# 010.net
KiCad netlist of a schematic drawn in EAGLE
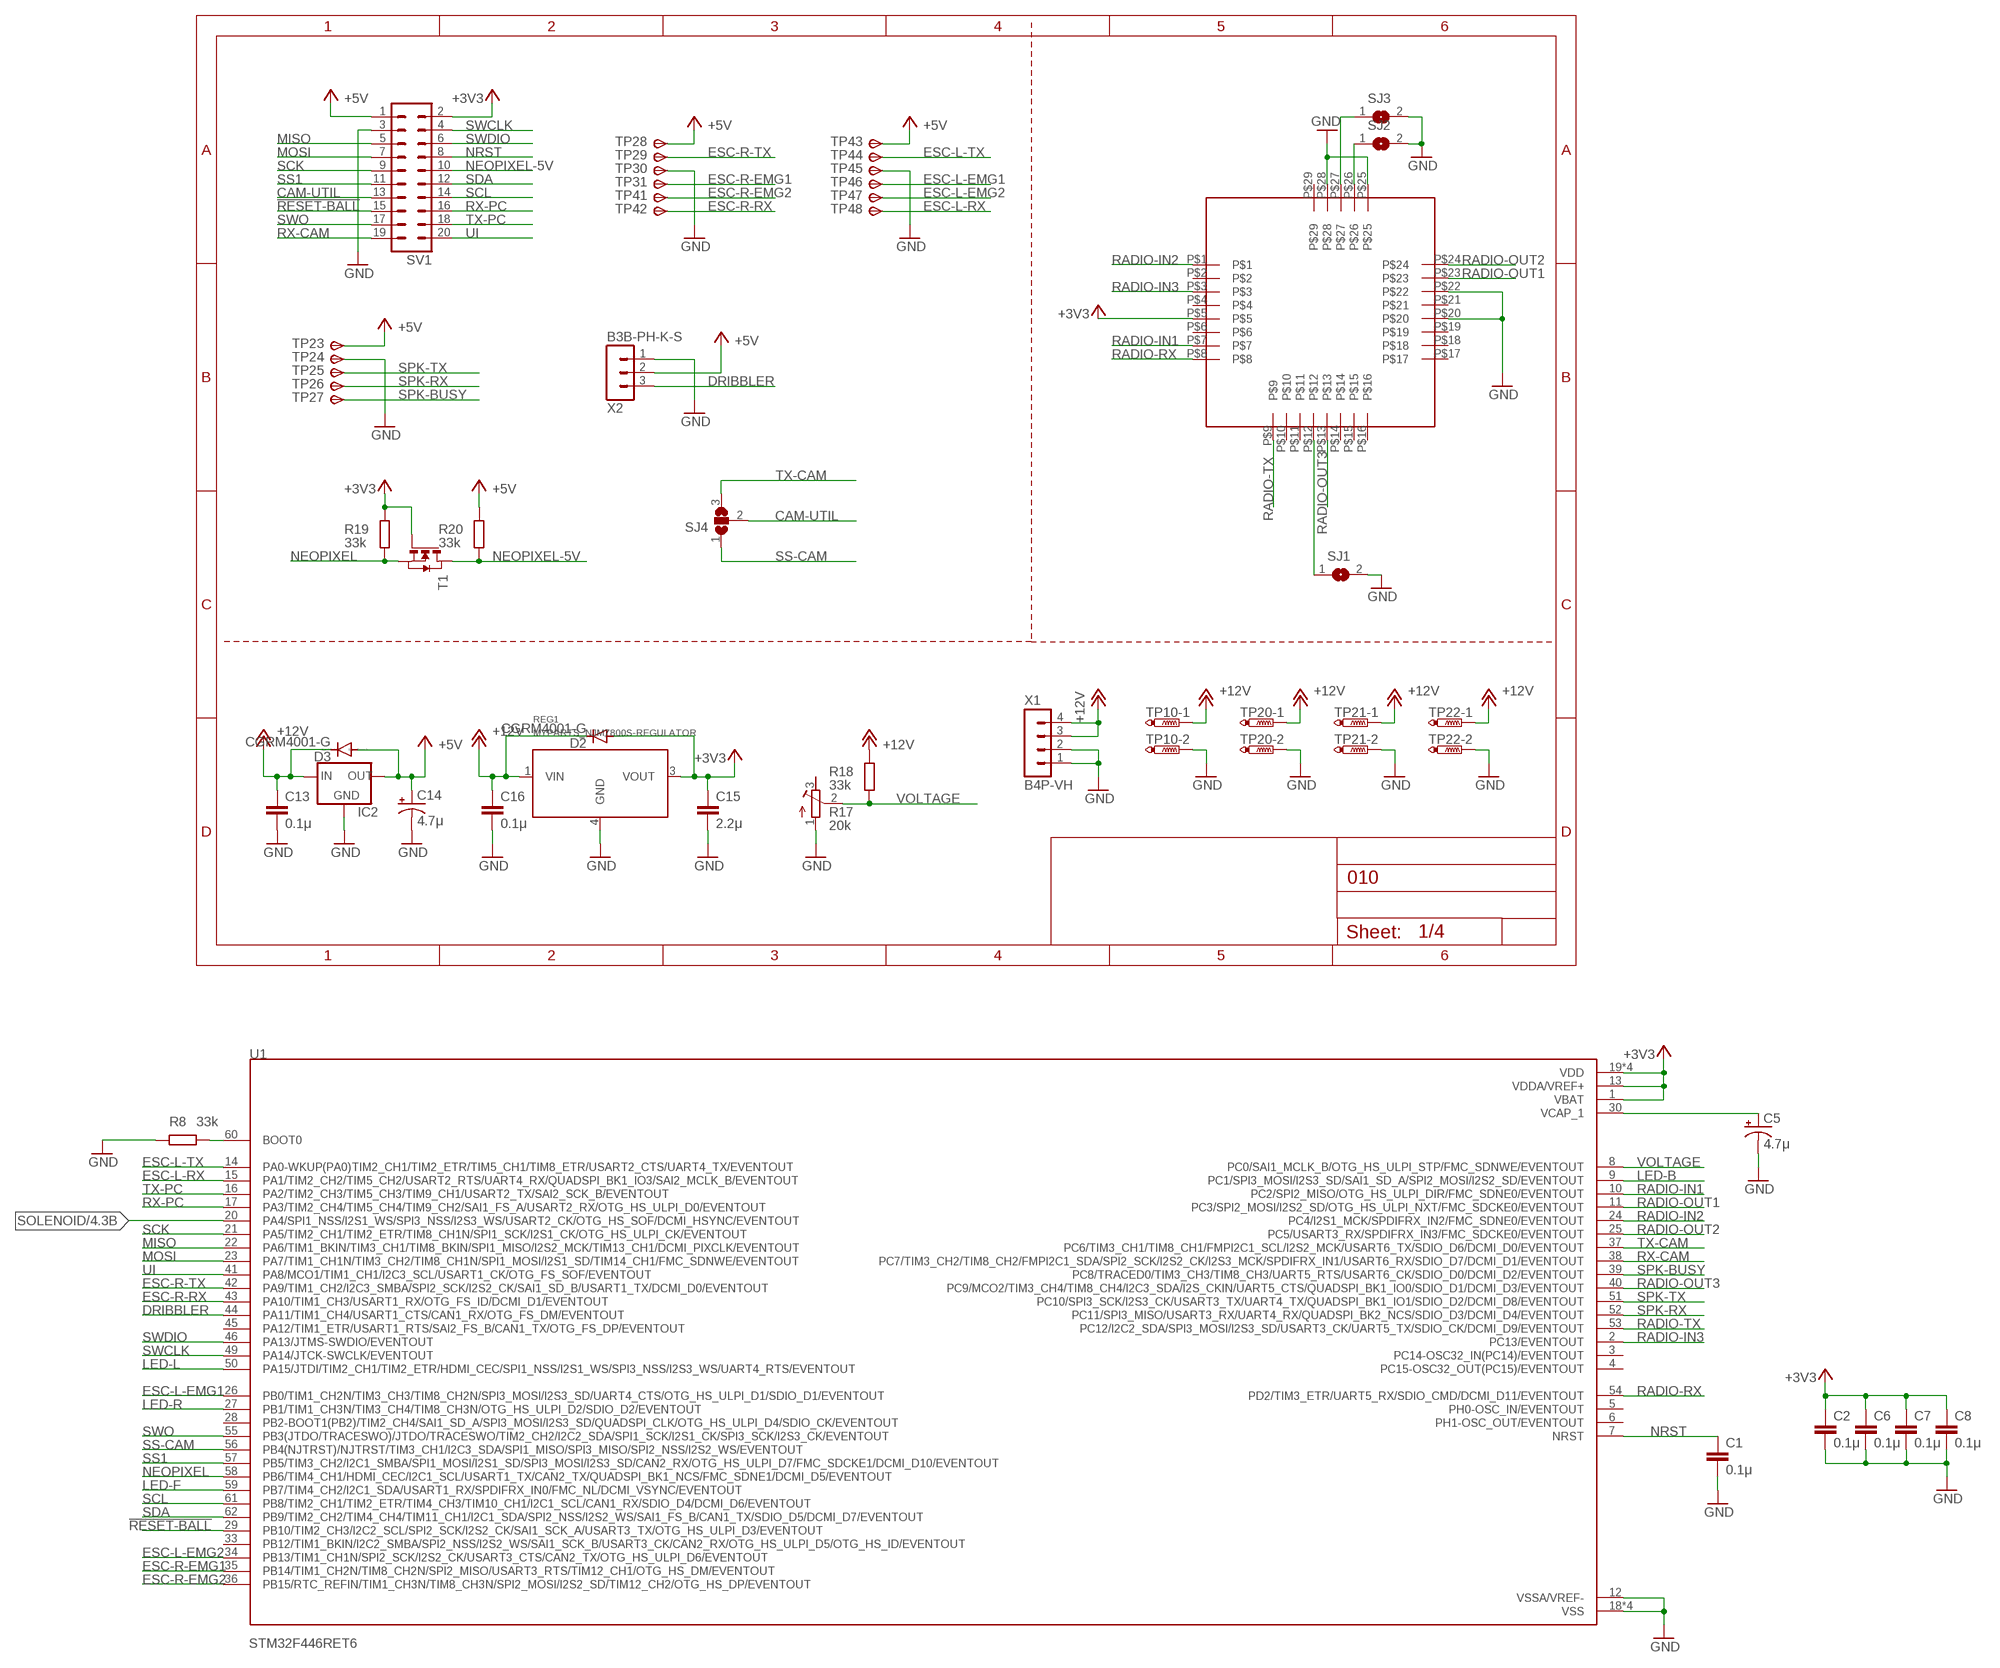
[diagram p0: schematic, sheet 1]
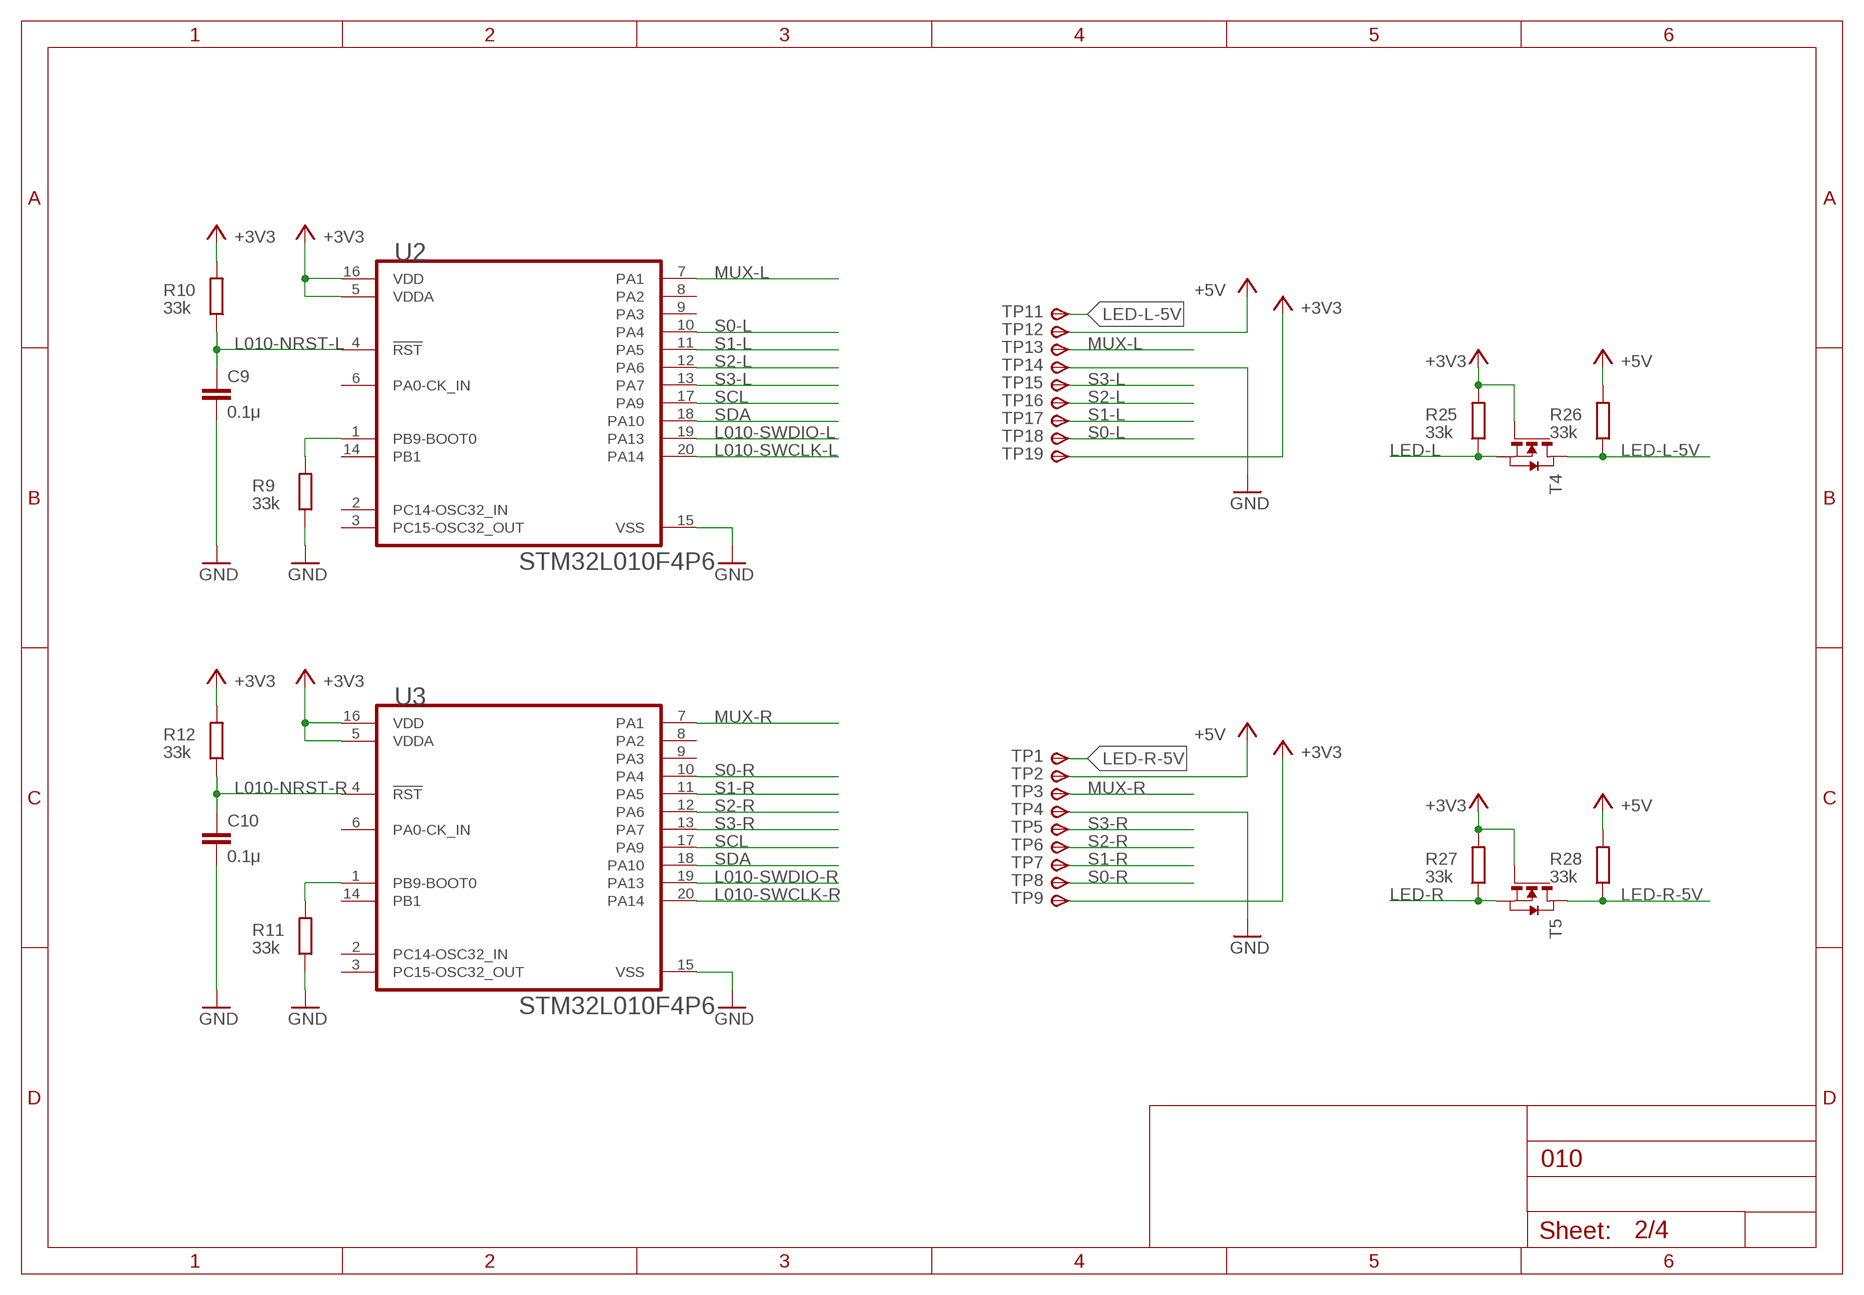
[diagram p1: schematic, sheet 2]
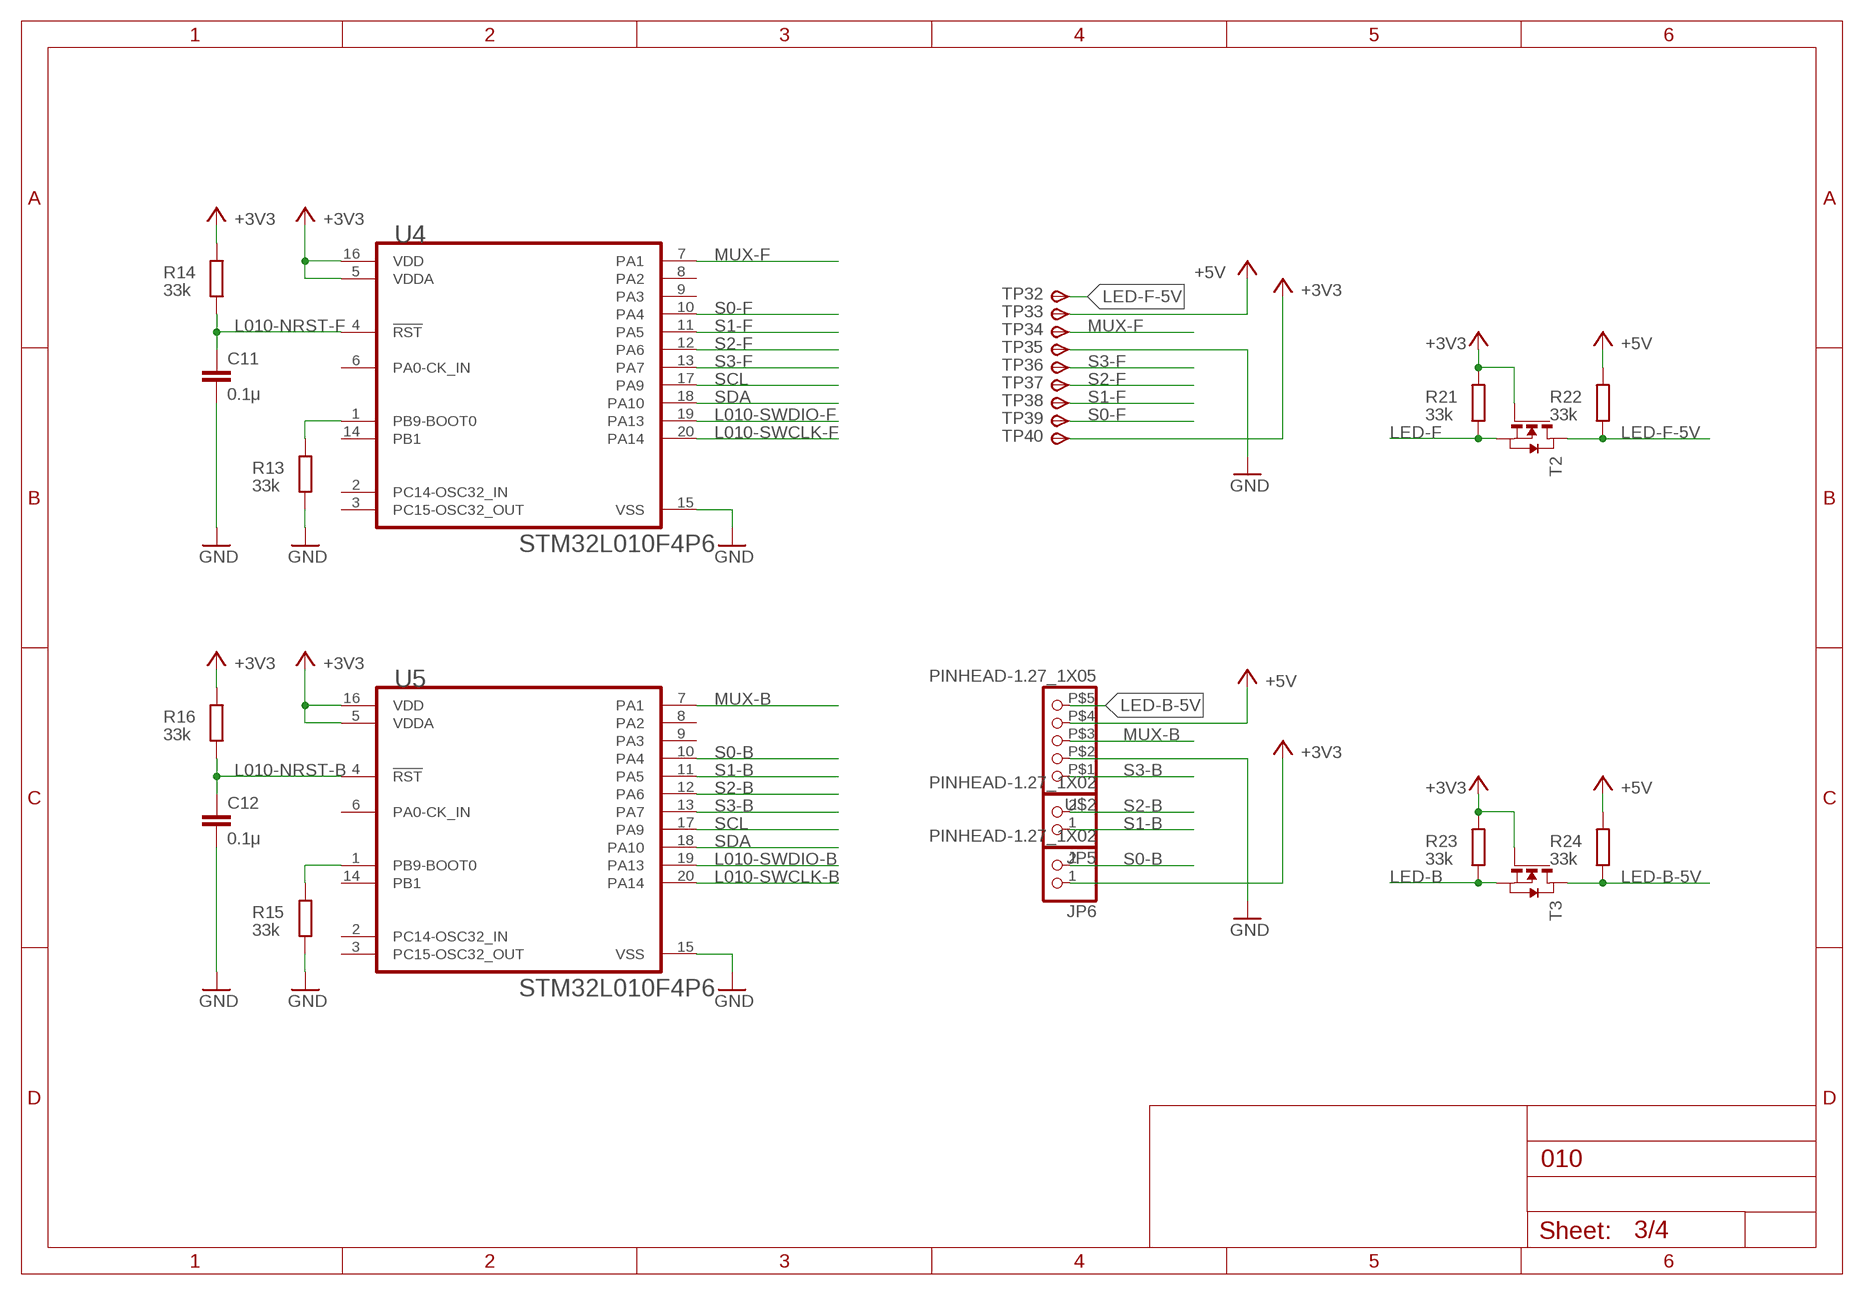
[diagram p2: schematic, sheet 3]
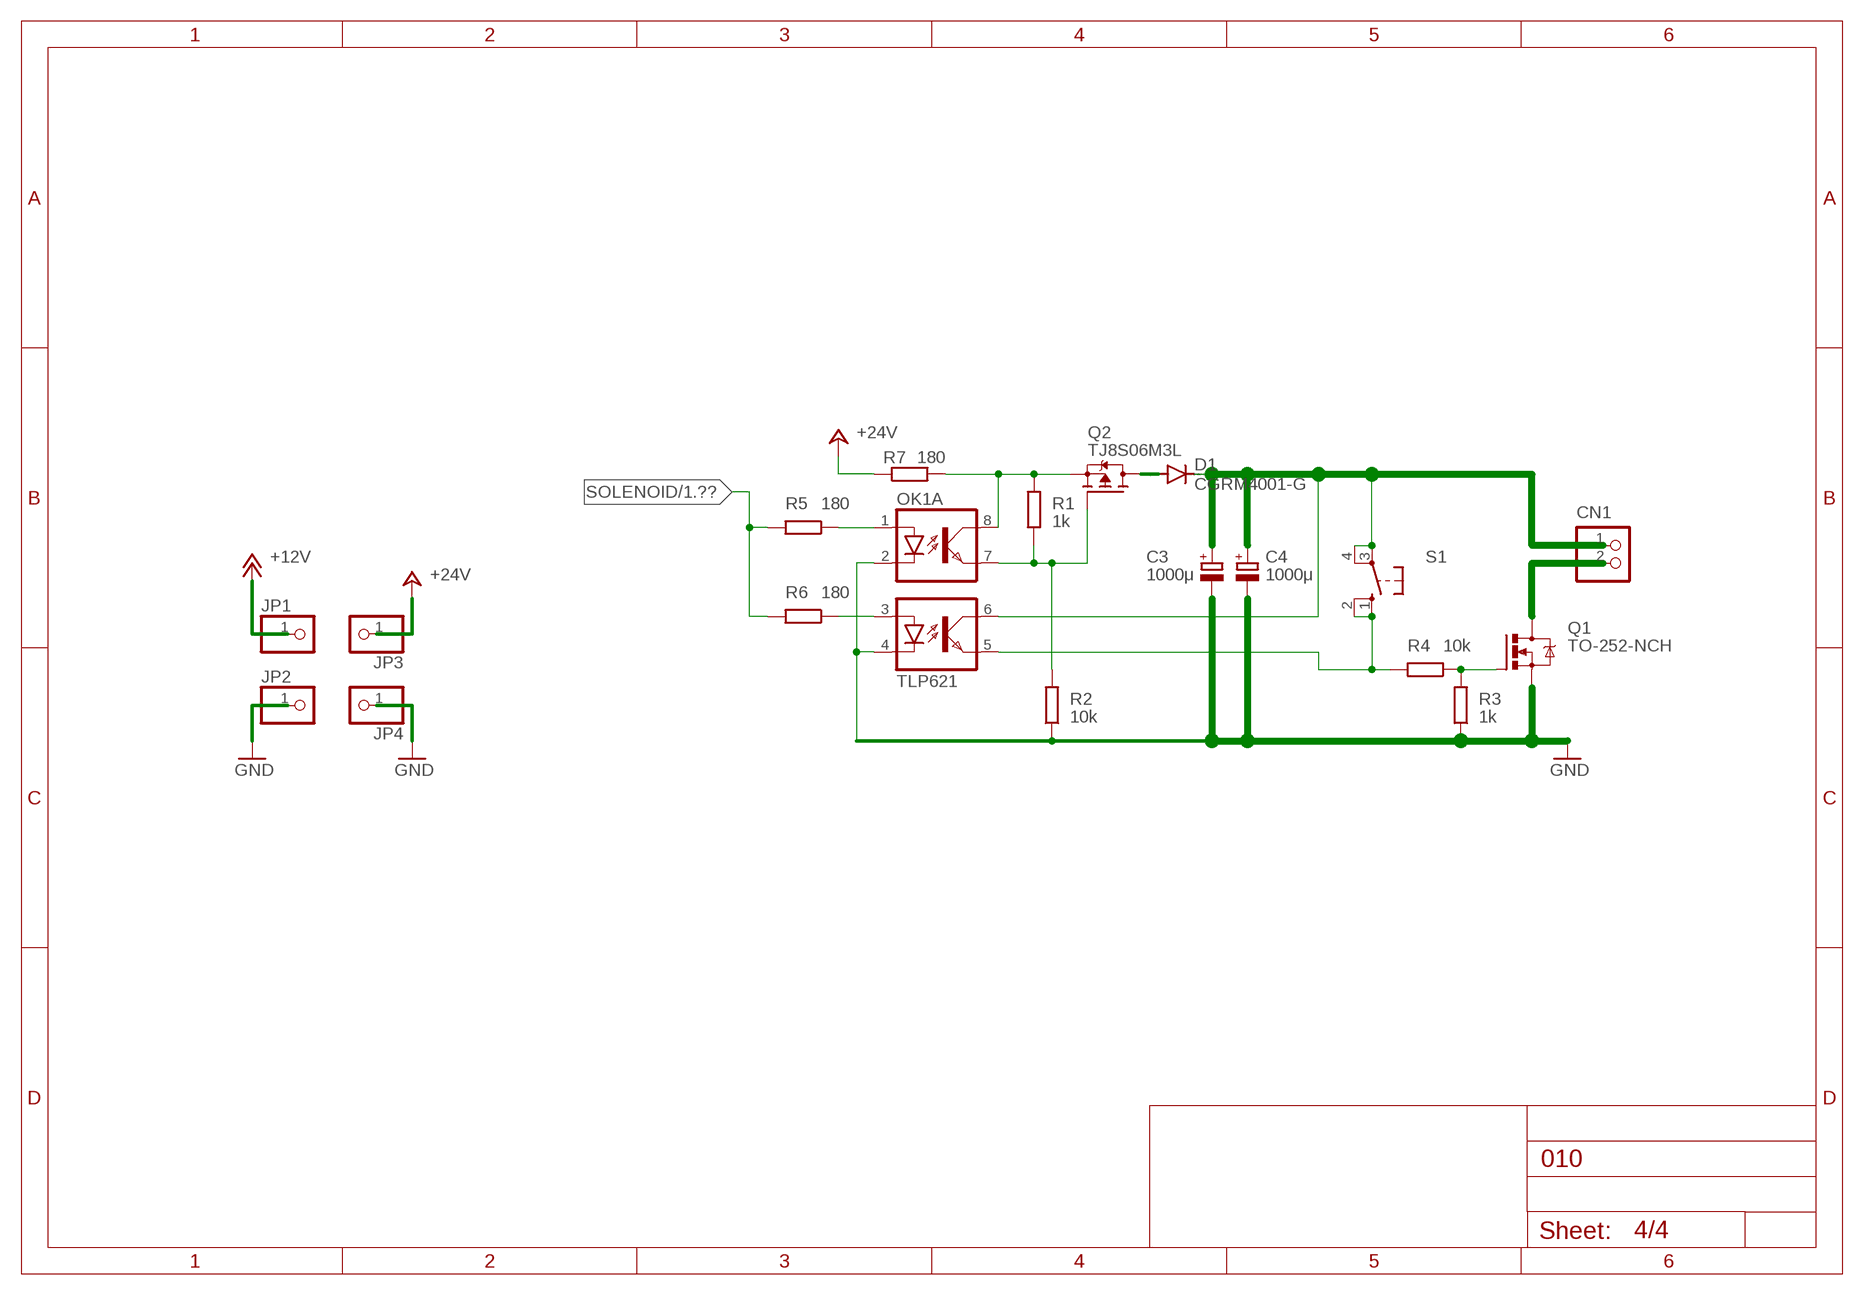
[diagram p3: schematic, sheet 4]

(export (version "E")
  (design (tool "Eeschema 10.0.6"))
  (components
    (comp (ref "C1")
      (value "0.1μ")
      (footprint "eagle-import:C1608")
      (libsource (lib "eagle-import") (part "C-EUC1608"))
    )
    (comp (ref "C2")
      (value "0.1μ")
      (footprint "eagle-import:C1608")
      (libsource (lib "eagle-import") (part "C-EUC1608"))
    )
    (comp (ref "C5")
      (value "4.7μ")
      (footprint "eagle-import:SANYO-OSCON_SMD_B6")
      (libsource (lib "eagle-import") (part "CPOL-USSANYO_SMD_B6"))
    )
    (comp (ref "C6")
      (value "0.1μ")
      (footprint "eagle-import:C1608")
      (libsource (lib "eagle-import") (part "C-EUC1608"))
    )
    (comp (ref "C7")
      (value "0.1μ")
      (footprint "eagle-import:C1608")
      (libsource (lib "eagle-import") (part "C-EUC1608"))
    )
    (comp (ref "C8")
      (value "0.1μ")
      (footprint "eagle-import:C1608")
      (libsource (lib "eagle-import") (part "C-EUC1608"))
    )
    (comp (ref "C13")
      (value "0.1μ")
      (footprint "eagle-import:C1608")
      (libsource (lib "eagle-import") (part "C-EUC1608"))
    )
    (comp (ref "C14")
      (value "4.7μ")
      (footprint "eagle-import:SANYO-OSCON_SMD_B6")
      (libsource (lib "eagle-import") (part "CPOL-USSANYO_SMD_B6"))
    )
    (comp (ref "C15")
      (value "2.2μ")
      (footprint "eagle-import:C1608")
      (libsource (lib "eagle-import") (part "C-EUC1608"))
    )
    (comp (ref "C16")
      (value "0.1μ")
      (footprint "eagle-import:C1608")
      (libsource (lib "eagle-import") (part "C-EUC1608"))
    )
    (comp (ref "D2")
      (value "CGRM4001-G")
      (footprint "eagle-import:SOD-123_MINI-SMA")
      (libsource (lib "eagle-import") (part "CGRM400-G1"))
    )
    (comp (ref "D3")
      (value "CGRM4001-G")
      (footprint "eagle-import:SOD-123_MINI-SMA")
      (libsource (lib "eagle-import") (part "CGRM400-G1"))
    )
    (comp (ref "IC2")
      (value "78XXS")
      (footprint "eagle-import:78XXS")
      (libsource (lib "eagle-import") (part "78XXS"))
    )
    (comp (ref "R8")
      (value "33k")
      (footprint "eagle-import:R0603")
      (libsource (lib "eagle-import") (part "R-EU_R0603"))
    )
    (comp (ref "R17")
      (value "20k")
      (footprint "eagle-import:RTRIM3296W")
      (libsource (lib "eagle-import") (part "R-TRIMM3296W"))
    )
    (comp (ref "R18")
      (value "33k")
      (footprint "eagle-import:R0603")
      (libsource (lib "eagle-import") (part "R-EU_R0603"))
    )
    (comp (ref "R19")
      (value "33k")
      (footprint "eagle-import:R0603")
      (libsource (lib "eagle-import") (part "R-EU_R0603"))
    )
    (comp (ref "R20")
      (value "33k")
      (footprint "eagle-import:R0603")
      (libsource (lib "eagle-import") (part "R-EU_R0603"))
    )
    (comp (ref "REG1")
      (value "MYPARTS_NJM7800S-REGULATOR")
      (footprint "eagle-import:MYPARTS_D-PAK_TO252AA")
      (libsource (lib "eagle-import") (part "MYPARTS_NJM7800S-REGULATOR"))
    )
    (comp (ref "SJ1") (value "SJ") (footprint "eagle-import:SJ") (libsource (lib "eagle-import") (part "SJ")))
    (comp (ref "SJ2") (value "SJ") (footprint "eagle-import:SJ") (libsource (lib "eagle-import") (part "SJ")))
    (comp (ref "SJ3") (value "SJ") (footprint "eagle-import:SJ") (libsource (lib "eagle-import") (part "SJ")))
    (comp (ref "SJ4")
      (value "SJ2W")
      (footprint "eagle-import:SJ_2")
      (libsource (lib "eagle-import") (part "SJ2W"))
    )
    (comp (ref "SV1")
      (value "ML20")
      (footprint "eagle-import:ML20")
      (libsource (lib "eagle-import") (part "ML20"))
    )
    (comp (ref "T1")
      (value "NMOSSOT23")
      (footprint "eagle-import:SOT-23")
      (libsource (lib "eagle-import") (part "NMOSSOT23"))
    )
    (comp (ref "TP10")
      (value "PTR2")
      (footprint "eagle-import:P2-38-17")
      (libsource (lib "eagle-import") (part "PTR2"))
    )
    (comp (ref "TP20")
      (value "PTR2")
      (footprint "eagle-import:P2-38-17")
      (libsource (lib "eagle-import") (part "PTR2"))
    )
    (comp (ref "TP21")
      (value "PTR2")
      (footprint "eagle-import:P2-38-17")
      (libsource (lib "eagle-import") (part "PTR2"))
    )
    (comp (ref "TP22")
      (value "PTR2")
      (footprint "eagle-import:P2-38-17")
      (libsource (lib "eagle-import") (part "PTR2"))
    )
    (comp (ref "TP23")
      (value "TPSTP09SQ")
      (footprint "eagle-import:TP09SQ")
      (libsource (lib "eagle-import") (part "TPSTP09SQ"))
    )
    (comp (ref "TP24")
      (value "TPSTP09R")
      (footprint "eagle-import:TP09R")
      (libsource (lib "eagle-import") (part "TPSTP09R"))
    )
    (comp (ref "TP25")
      (value "TPSTP09R")
      (footprint "eagle-import:TP09R")
      (libsource (lib "eagle-import") (part "TPSTP09R"))
    )
    (comp (ref "TP26")
      (value "TPSTP09R")
      (footprint "eagle-import:TP09R")
      (libsource (lib "eagle-import") (part "TPSTP09R"))
    )
    (comp (ref "TP27")
      (value "TPSTP09R")
      (footprint "eagle-import:TP09R")
      (libsource (lib "eagle-import") (part "TPSTP09R"))
    )
    (comp (ref "TP28")
      (value "TPSTP09SQ")
      (footprint "eagle-import:TP09SQ")
      (libsource (lib "eagle-import") (part "TPSTP09SQ"))
    )
    (comp (ref "TP29")
      (value "TPSTP09R")
      (footprint "eagle-import:TP09R")
      (libsource (lib "eagle-import") (part "TPSTP09R"))
    )
    (comp (ref "TP30")
      (value "TPSTP09R")
      (footprint "eagle-import:TP09R")
      (libsource (lib "eagle-import") (part "TPSTP09R"))
    )
    (comp (ref "TP31")
      (value "TPSTP09R")
      (footprint "eagle-import:TP09R")
      (libsource (lib "eagle-import") (part "TPSTP09R"))
    )
    (comp (ref "TP41")
      (value "TPSTP09R")
      (footprint "eagle-import:TP09R")
      (libsource (lib "eagle-import") (part "TPSTP09R"))
    )
    (comp (ref "TP42")
      (value "TPSTP09R")
      (footprint "eagle-import:TP09R")
      (libsource (lib "eagle-import") (part "TPSTP09R"))
    )
    (comp (ref "TP43")
      (value "TPSTP09SQ")
      (footprint "eagle-import:TP09SQ")
      (libsource (lib "eagle-import") (part "TPSTP09SQ"))
    )
    (comp (ref "TP44")
      (value "TPSTP09R")
      (footprint "eagle-import:TP09R")
      (libsource (lib "eagle-import") (part "TPSTP09R"))
    )
    (comp (ref "TP45")
      (value "TPSTP09R")
      (footprint "eagle-import:TP09R")
      (libsource (lib "eagle-import") (part "TPSTP09R"))
    )
    (comp (ref "TP46")
      (value "TPSTP09R")
      (footprint "eagle-import:TP09R")
      (libsource (lib "eagle-import") (part "TPSTP09R"))
    )
    (comp (ref "TP47")
      (value "TPSTP09R")
      (footprint "eagle-import:TP09R")
      (libsource (lib "eagle-import") (part "TPSTP09R"))
    )
    (comp (ref "TP48")
      (value "TPSTP09R")
      (footprint "eagle-import:TP09R")
      (libsource (lib "eagle-import") (part "TPSTP09R"))
    )
    (comp (ref "U$1")
      (value "LITE")
      (footprint "eagle-import:LITE")
      (libsource (lib "eagle-import") (part "LITE"))
    )
    (comp (ref "U1")
      (value "STM32F446RET6")
      (footprint "eagle-import:QFP50P1200X1200X160-64N")
      (fields
        (field (name "DIGI-KEY_PART_NUMBER") "497-STM32F446RET6TR-ND")
        (field (name "MF") "STMicroelectronics")
      )
      (libsource (lib "eagle-import") (part "STM32F446RET6"))
    )
    (comp (ref "X1")
      (value "B4P-VH")
      (footprint "eagle-import:B4P-VH")
      (libsource (lib "eagle-import") (part "B4P-VH"))
    )
    (comp (ref "X2")
      (value "B3B-PH-K-S")
      (footprint "eagle-import:B3B-PH-K-S")
      (libsource (lib "eagle-import") (part "B3B-PH-K-S"))
    )
    (comp (ref "C3")
      (value "1000μ")
      (footprint "eagle-import:C12.5")
      (libsource (lib "eagle-import") (part "C12.5"))
    )
    (comp (ref "C4")
      (value "1000μ")
      (footprint "eagle-import:C12.5")
      (libsource (lib "eagle-import") (part "C12.5"))
    )
    (comp (ref "CN1")
      (value "B2B-PH-K-S")
      (footprint "eagle-import:B2B-PH-K-S")
      (libsource (lib "eagle-import") (part "B2B-PH-K-S"))
    )
    (comp (ref "D1")
      (value "CGRM4001-G")
      (footprint "eagle-import:SOD-123_MINI-SMA")
      (libsource (lib "eagle-import") (part "CGRM400-G1"))
    )
    (comp (ref "JP1")
      (value "PINHD-1X1")
      (footprint "eagle-import:1X01")
      (libsource (lib "eagle-import") (part "PINHD-1X1"))
    )
    (comp (ref "JP2")
      (value "PINHD-1X1")
      (footprint "eagle-import:1X01")
      (libsource (lib "eagle-import") (part "PINHD-1X1"))
    )
    (comp (ref "JP3")
      (value "PINHD-1X1")
      (footprint "eagle-import:1X01")
      (libsource (lib "eagle-import") (part "PINHD-1X1"))
    )
    (comp (ref "JP4")
      (value "PINHD-1X1")
      (footprint "eagle-import:1X01")
      (libsource (lib "eagle-import") (part "PINHD-1X1"))
    )
    (comp (ref "OK1")
      (value "TLP621")
      (footprint "eagle-import:DIL08")
      (libsource (lib "eagle-import") (part "PC827"))
    )
    (comp (ref "Q1")
      (value "TO-252-NCH")
      (footprint "eagle-import:D-PAK_TO252AA")
      (libsource (lib "eagle-import") (part "TO-252-NCH"))
    )
    (comp (ref "Q2")
      (value "TJ8S06M3L")
      (footprint "eagle-import:TO252")
      (libsource (lib "eagle-import") (part "SPD30P06PTO252"))
    )
    (comp (ref "R1")
      (value "1k")
      (footprint "eagle-import:R0603")
      (libsource (lib "eagle-import") (part "R-EU_R0603"))
    )
    (comp (ref "R2")
      (value "10k")
      (footprint "eagle-import:R0603")
      (libsource (lib "eagle-import") (part "R-EU_R0603"))
    )
    (comp (ref "R3")
      (value "1k")
      (footprint "eagle-import:R0603")
      (libsource (lib "eagle-import") (part "R-EU_R0603"))
    )
    (comp (ref "R4")
      (value "10k")
      (footprint "eagle-import:R0603")
      (libsource (lib "eagle-import") (part "R-EU_R0603"))
    )
    (comp (ref "R5")
      (value "180")
      (footprint "eagle-import:R0603")
      (libsource (lib "eagle-import") (part "R-EU_R0603"))
    )
    (comp (ref "R6")
      (value "180")
      (footprint "eagle-import:R0603")
      (libsource (lib "eagle-import") (part "R-EU_R0603"))
    )
    (comp (ref "R7")
      (value "180")
      (footprint "eagle-import:0204_7")
      (libsource (lib "eagle-import") (part "R-EU_0204/7"))
    )
    (comp (ref "S1")
      (value "10-XX")
      (footprint "eagle-import:B3F-10XX")
      (fields (field (name "MPN") "B3F-1000"))
      (libsource (lib "eagle-import") (part "10-XX"))
    )
    (comp (ref "C9")
      (value "0.1μ")
      (footprint "eagle-import:C1608")
      (libsource (lib "eagle-import") (part "C-EUC1608"))
    )
    (comp (ref "C10")
      (value "0.1μ")
      (footprint "eagle-import:C1608")
      (libsource (lib "eagle-import") (part "C-EUC1608"))
    )
    (comp (ref "R9")
      (value "33k")
      (footprint "eagle-import:R0603")
      (libsource (lib "eagle-import") (part "R-EU_R0603"))
    )
    (comp (ref "R10")
      (value "33k")
      (footprint "eagle-import:R0603")
      (libsource (lib "eagle-import") (part "R-EU_R0603"))
    )
    (comp (ref "R11")
      (value "33k")
      (footprint "eagle-import:R0603")
      (libsource (lib "eagle-import") (part "R-EU_R0603"))
    )
    (comp (ref "R12")
      (value "33k")
      (footprint "eagle-import:R0603")
      (libsource (lib "eagle-import") (part "R-EU_R0603"))
    )
    (comp (ref "R25")
      (value "33k")
      (footprint "eagle-import:R0603")
      (libsource (lib "eagle-import") (part "R-EU_R0603"))
    )
    (comp (ref "R26")
      (value "33k")
      (footprint "eagle-import:R0603")
      (libsource (lib "eagle-import") (part "R-EU_R0603"))
    )
    (comp (ref "R27")
      (value "33k")
      (footprint "eagle-import:R0603")
      (libsource (lib "eagle-import") (part "R-EU_R0603"))
    )
    (comp (ref "R28")
      (value "33k")
      (footprint "eagle-import:R0603")
      (libsource (lib "eagle-import") (part "R-EU_R0603"))
    )
    (comp (ref "T4")
      (value "NMOSSOT23")
      (footprint "eagle-import:SOT-23")
      (libsource (lib "eagle-import") (part "NMOSSOT23"))
    )
    (comp (ref "T5")
      (value "NMOSSOT23")
      (footprint "eagle-import:SOT-23")
      (libsource (lib "eagle-import") (part "NMOSSOT23"))
    )
    (comp (ref "TP1")
      (value "TPSTP09SQ")
      (footprint "eagle-import:TP09SQ")
      (libsource (lib "eagle-import") (part "TPSTP09SQ"))
    )
    (comp (ref "TP2")
      (value "TPSTP09R")
      (footprint "eagle-import:TP09R")
      (libsource (lib "eagle-import") (part "TPSTP09R"))
    )
    (comp (ref "TP3")
      (value "TPSTP09R")
      (footprint "eagle-import:TP09R")
      (libsource (lib "eagle-import") (part "TPSTP09R"))
    )
    (comp (ref "TP4")
      (value "TPSTP09R")
      (footprint "eagle-import:TP09R")
      (libsource (lib "eagle-import") (part "TPSTP09R"))
    )
    (comp (ref "TP5")
      (value "TPSTP09R")
      (footprint "eagle-import:TP09R")
      (libsource (lib "eagle-import") (part "TPSTP09R"))
    )
    (comp (ref "TP6")
      (value "TPSTP09R")
      (footprint "eagle-import:TP09R")
      (libsource (lib "eagle-import") (part "TPSTP09R"))
    )
    (comp (ref "TP7")
      (value "TPSTP09R")
      (footprint "eagle-import:TP09R")
      (libsource (lib "eagle-import") (part "TPSTP09R"))
    )
    (comp (ref "TP8")
      (value "TPSTP09R")
      (footprint "eagle-import:TP09R")
      (libsource (lib "eagle-import") (part "TPSTP09R"))
    )
    (comp (ref "TP9")
      (value "TPSTP09R")
      (footprint "eagle-import:TP09R")
      (libsource (lib "eagle-import") (part "TPSTP09R"))
    )
    (comp (ref "TP11")
      (value "TPSTP09SQ")
      (footprint "eagle-import:TP09SQ")
      (libsource (lib "eagle-import") (part "TPSTP09SQ"))
    )
    (comp (ref "TP12")
      (value "TPSTP09R")
      (footprint "eagle-import:TP09R")
      (libsource (lib "eagle-import") (part "TPSTP09R"))
    )
    (comp (ref "TP13")
      (value "TPSTP09R")
      (footprint "eagle-import:TP09R")
      (libsource (lib "eagle-import") (part "TPSTP09R"))
    )
    (comp (ref "TP14")
      (value "TPSTP09R")
      (footprint "eagle-import:TP09R")
      (libsource (lib "eagle-import") (part "TPSTP09R"))
    )
    (comp (ref "TP15")
      (value "TPSTP09R")
      (footprint "eagle-import:TP09R")
      (libsource (lib "eagle-import") (part "TPSTP09R"))
    )
    (comp (ref "TP16")
      (value "TPSTP09R")
      (footprint "eagle-import:TP09R")
      (libsource (lib "eagle-import") (part "TPSTP09R"))
    )
    (comp (ref "TP17")
      (value "TPSTP09R")
      (footprint "eagle-import:TP09R")
      (libsource (lib "eagle-import") (part "TPSTP09R"))
    )
    (comp (ref "TP18")
      (value "TPSTP09R")
      (footprint "eagle-import:TP09R")
      (libsource (lib "eagle-import") (part "TPSTP09R"))
    )
    (comp (ref "TP19")
      (value "TPSTP09R")
      (footprint "eagle-import:TP09R")
      (libsource (lib "eagle-import") (part "TPSTP09R"))
    )
    (comp (ref "U2")
      (value "STMICROELECTRONICS_STM32L010F4P6STMICROELECTRONICS_STM32L010F4P6_0_2")
      (footprint "eagle-import:STMICROELECTRONICS_STM32L010F4P6_2")
      (fields
        (field (name "DIGIKEY_PART_NUMBER") "497-19364-ND")
        (field (name "MF") "STMicroelectronics")
        (field (name "MOUSER_PART_NUMBER") "511-STM32L010F4P6")
      )
      (libsource (lib "eagle-import") (part "STMICROELECTRONICS_STM32L010F4P6STMICROELECTRONICS_STM32L010F4P6_0_2"))
    )
    (comp (ref "U3")
      (value "STMICROELECTRONICS_STM32L010F4P6STMICROELECTRONICS_STM32L010F4P6_0_2")
      (footprint "eagle-import:STMICROELECTRONICS_STM32L010F4P6_2")
      (fields
        (field (name "DIGIKEY_PART_NUMBER") "497-19364-ND")
        (field (name "MF") "STMicroelectronics")
        (field (name "MOUSER_PART_NUMBER") "511-STM32L010F4P6")
      )
      (libsource (lib "eagle-import") (part "STMICROELECTRONICS_STM32L010F4P6STMICROELECTRONICS_STM32L010F4P6_0_2"))
    )
    (comp (ref "C11")
      (value "0.1μ")
      (footprint "eagle-import:C1608")
      (libsource (lib "eagle-import") (part "C-EUC1608"))
    )
    (comp (ref "C12")
      (value "0.1μ")
      (footprint "eagle-import:C1608")
      (libsource (lib "eagle-import") (part "C-EUC1608"))
    )
    (comp (ref "JP5")
      (value "PINHEAD-1.27_1X02")
      (footprint "eagle-import:PINHEAD-1.27_1X02")
      (libsource (lib "eagle-import") (part "PINHEAD-1.27_1X02"))
    )
    (comp (ref "JP6")
      (value "PINHEAD-1.27_1X02")
      (footprint "eagle-import:PINHEAD-1.27_1X02")
      (libsource (lib "eagle-import") (part "PINHEAD-1.27_1X02"))
    )
    (comp (ref "R13")
      (value "33k")
      (footprint "eagle-import:R0603")
      (libsource (lib "eagle-import") (part "R-EU_R0603"))
    )
    (comp (ref "R14")
      (value "33k")
      (footprint "eagle-import:R0603")
      (libsource (lib "eagle-import") (part "R-EU_R0603"))
    )
    (comp (ref "R15")
      (value "33k")
      (footprint "eagle-import:R0603")
      (libsource (lib "eagle-import") (part "R-EU_R0603"))
    )
    (comp (ref "R16")
      (value "33k")
      (footprint "eagle-import:R0603")
      (libsource (lib "eagle-import") (part "R-EU_R0603"))
    )
    (comp (ref "R21")
      (value "33k")
      (footprint "eagle-import:R0603")
      (libsource (lib "eagle-import") (part "R-EU_R0603"))
    )
    (comp (ref "R22")
      (value "33k")
      (footprint "eagle-import:R0603")
      (libsource (lib "eagle-import") (part "R-EU_R0603"))
    )
    (comp (ref "R23")
      (value "33k")
      (footprint "eagle-import:R0603")
      (libsource (lib "eagle-import") (part "R-EU_R0603"))
    )
    (comp (ref "R24")
      (value "33k")
      (footprint "eagle-import:R0603")
      (libsource (lib "eagle-import") (part "R-EU_R0603"))
    )
    (comp (ref "T2")
      (value "NMOSSOT23")
      (footprint "eagle-import:SOT-23")
      (libsource (lib "eagle-import") (part "NMOSSOT23"))
    )
    (comp (ref "T3")
      (value "NMOSSOT23")
      (footprint "eagle-import:SOT-23")
      (libsource (lib "eagle-import") (part "NMOSSOT23"))
    )
    (comp (ref "TP32")
      (value "TPSTP09SQ")
      (footprint "eagle-import:TP09SQ")
      (libsource (lib "eagle-import") (part "TPSTP09SQ"))
    )
    (comp (ref "TP33")
      (value "TPSTP09R")
      (footprint "eagle-import:TP09R")
      (libsource (lib "eagle-import") (part "TPSTP09R"))
    )
    (comp (ref "TP34")
      (value "TPSTP09R")
      (footprint "eagle-import:TP09R")
      (libsource (lib "eagle-import") (part "TPSTP09R"))
    )
    (comp (ref "TP35")
      (value "TPSTP09R")
      (footprint "eagle-import:TP09R")
      (libsource (lib "eagle-import") (part "TPSTP09R"))
    )
    (comp (ref "TP36")
      (value "TPSTP09R")
      (footprint "eagle-import:TP09R")
      (libsource (lib "eagle-import") (part "TPSTP09R"))
    )
    (comp (ref "TP37")
      (value "TPSTP09R")
      (footprint "eagle-import:TP09R")
      (libsource (lib "eagle-import") (part "TPSTP09R"))
    )
    (comp (ref "TP38")
      (value "TPSTP09R")
      (footprint "eagle-import:TP09R")
      (libsource (lib "eagle-import") (part "TPSTP09R"))
    )
    (comp (ref "TP39")
      (value "TPSTP09R")
      (footprint "eagle-import:TP09R")
      (libsource (lib "eagle-import") (part "TPSTP09R"))
    )
    (comp (ref "TP40")
      (value "TPSTP09R")
      (footprint "eagle-import:TP09R")
      (libsource (lib "eagle-import") (part "TPSTP09R"))
    )
    (comp (ref "U$2")
      (value "PINHEAD-1.27_1X05")
      (footprint "eagle-import:PINHEAD-1.27_1X05")
      (libsource (lib "eagle-import") (part "PINHEAD-1.27_1X05"))
    )
    (comp (ref "U4")
      (value "STMICROELECTRONICS_STM32L010F4P6STMICROELECTRONICS_STM32L010F4P6_0_2")
      (footprint "eagle-import:STMICROELECTRONICS_STM32L010F4P6_2")
      (fields
        (field (name "DIGIKEY_PART_NUMBER") "497-19364-ND")
        (field (name "MF") "STMicroelectronics")
        (field (name "MOUSER_PART_NUMBER") "511-STM32L010F4P6")
      )
      (libsource (lib "eagle-import") (part "STMICROELECTRONICS_STM32L010F4P6STMICROELECTRONICS_STM32L010F4P6_0_2"))
    )
    (comp (ref "U5")
      (value "STMICROELECTRONICS_STM32L010F4P6STMICROELECTRONICS_STM32L010F4P6_0_2")
      (footprint "eagle-import:STMICROELECTRONICS_STM32L010F4P6_2")
      (fields
        (field (name "DIGIKEY_PART_NUMBER") "497-19364-ND")
        (field (name "MF") "STMicroelectronics")
        (field (name "MOUSER_PART_NUMBER") "511-STM32L010F4P6")
      )
      (libsource (lib "eagle-import") (part "STMICROELECTRONICS_STM32L010F4P6STMICROELECTRONICS_STM32L010F4P6_0_2"))
    )
  )
  (nets
    (net (code "1") (name "+3V3") (class "Default")
      (node (ref "C15") (pin "1") (pinfunction "1_1") (pintype "passive"))
      (node (ref "C2") (pin "1") (pinfunction "1_1") (pintype "passive"))
      (node (ref "C6") (pin "1") (pinfunction "1_1") (pintype "passive"))
      (node (ref "C7") (pin "1") (pinfunction "1_1") (pintype "passive"))
      (node (ref "C8") (pin "1") (pinfunction "1_1") (pintype "passive"))
      (node (ref "D2") (pin "A") (pinfunction "A_A") (pintype "passive"))
      (node (ref "JP6") (pin "1") (pinfunction "1_1") (pintype "passive"))
      (node (ref "R10") (pin "2") (pinfunction "2_2") (pintype "passive"))
      (node (ref "R12") (pin "2") (pinfunction "2_2") (pintype "passive"))
      (node (ref "R14") (pin "2") (pinfunction "2_2") (pintype "passive"))
      (node (ref "R16") (pin "2") (pinfunction "2_2") (pintype "passive"))
      (node (ref "R19") (pin "2") (pinfunction "2_2") (pintype "passive"))
      (node (ref "R21") (pin "2") (pinfunction "2_2") (pintype "passive"))
      (node (ref "R23") (pin "2") (pinfunction "2_2") (pintype "passive"))
      (node (ref "R25") (pin "2") (pinfunction "2_2") (pintype "passive"))
      (node (ref "R27") (pin "2") (pinfunction "2_2") (pintype "passive"))
      (node (ref "REG1") (pin "3") (pinfunction "VOUT_3") (pintype "passive"))
      (node (ref "SV1") (pin "2") (pinfunction "2_2") (pintype "passive"))
      (node (ref "T1") (pin "3") (pinfunction "G_3") (pintype "passive"))
      (node (ref "T2") (pin "3") (pinfunction "G_3") (pintype "passive"))
      (node (ref "T3") (pin "3") (pinfunction "G_3") (pintype "passive"))
      (node (ref "T4") (pin "3") (pinfunction "G_3") (pintype "passive"))
      (node (ref "T5") (pin "3") (pinfunction "G_3") (pintype "passive"))
      (node (ref "TP19") (pin "TP") (pinfunction "PP_TP") (pintype "input"))
      (node (ref "TP40") (pin "TP") (pinfunction "PP_TP") (pintype "input"))
      (node (ref "TP9") (pin "TP") (pinfunction "PP_TP") (pintype "input"))
      (node (ref "U$1") (pin "P$5") (pinfunction "P$5_P$5") (pintype "bidirectional"))
      (node (ref "U1") (pin "1") (pinfunction "VBAT_1") (pintype "power_in"))
      (node (ref "U1") (pin "13") (pinfunction "VDDA/VREF+_13") (pintype "power_in"))
      (node (ref "U1") (pin "19") (pinfunction "VDD_19") (pintype "power_in"))
      (node (ref "U1") (pin "32") (pinfunction "VDD_32") (pintype "power_in"))
      (node (ref "U1") (pin "48") (pinfunction "VDD_48") (pintype "power_in"))
      (node (ref "U1") (pin "64") (pinfunction "VDD_64") (pintype "power_in"))
      (node (ref "U2") (pin "16") (pinfunction "VDD_16") (pintype "power_in"))
      (node (ref "U2") (pin "5") (pinfunction "VDDA_5") (pintype "power_in"))
      (node (ref "U3") (pin "16") (pinfunction "VDD_16") (pintype "power_in"))
      (node (ref "U3") (pin "5") (pinfunction "VDDA_5") (pintype "power_in"))
      (node (ref "U4") (pin "16") (pinfunction "VDD_16") (pintype "power_in"))
      (node (ref "U4") (pin "5") (pinfunction "VDDA_5") (pintype "power_in"))
      (node (ref "U5") (pin "16") (pinfunction "VDD_16") (pintype "power_in"))
      (node (ref "U5") (pin "5") (pinfunction "VDDA_5") (pintype "power_in"))
    )
    (net (code "2") (name "+5V") (class "Default")
      (node (ref "C14") (pin "+") (pinfunction "+_+") (pintype "passive"))
      (node (ref "D3") (pin "A") (pinfunction "A_A") (pintype "passive"))
      (node (ref "IC2") (pin "OUT") (pinfunction "OUT_OUT") (pintype "passive"))
      (node (ref "R20") (pin "2") (pinfunction "2_2") (pintype "passive"))
      (node (ref "R22") (pin "2") (pinfunction "2_2") (pintype "passive"))
      (node (ref "R24") (pin "2") (pinfunction "2_2") (pintype "passive"))
      (node (ref "R26") (pin "2") (pinfunction "2_2") (pintype "passive"))
      (node (ref "R28") (pin "2") (pinfunction "2_2") (pintype "passive"))
      (node (ref "SV1") (pin "1") (pinfunction "1_1") (pintype "passive"))
      (node (ref "TP12") (pin "TP") (pinfunction "PP_TP") (pintype "input"))
      (node (ref "TP2") (pin "TP") (pinfunction "PP_TP") (pintype "input"))
      (node (ref "TP23") (pin "TP") (pinfunction "PP_TP") (pintype "input"))
      (node (ref "TP28") (pin "TP") (pinfunction "PP_TP") (pintype "input"))
      (node (ref "TP33") (pin "TP") (pinfunction "PP_TP") (pintype "input"))
      (node (ref "TP43") (pin "TP") (pinfunction "PP_TP") (pintype "input"))
      (node (ref "U$2") (pin "P$4") (pinfunction "4_P$4") (pintype "passive"))
      (node (ref "X2") (pin "2") (pinfunction "2_2") (pintype "passive"))
    )
    (net (code "3") (name "+12V") (class "Default")
      (node (ref "C13") (pin "1") (pinfunction "1_1") (pintype "passive"))
      (node (ref "C16") (pin "1") (pinfunction "1_1") (pintype "passive"))
      (node (ref "D2") (pin "C") (pinfunction "C_C") (pintype "passive"))
      (node (ref "D3") (pin "C") (pinfunction "C_C") (pintype "passive"))
      (node (ref "IC2") (pin "IN") (pinfunction "IN_IN") (pintype "input"))
      (node (ref "JP1") (pin "1") (pinfunction "1_1") (pintype "passive"))
      (node (ref "R18") (pin "2") (pinfunction "2_2") (pintype "passive"))
      (node (ref "REG1") (pin "1") (pinfunction "VIN_1") (pintype "passive"))
      (node (ref "TP10") (pin "TP-1") (pinfunction "TP_TP-1") (pintype "input"))
      (node (ref "TP20") (pin "TP-1") (pinfunction "TP_TP-1") (pintype "input"))
      (node (ref "TP21") (pin "TP-1") (pinfunction "TP_TP-1") (pintype "input"))
      (node (ref "TP22") (pin "TP-1") (pinfunction "TP_TP-1") (pintype "input"))
      (node (ref "X1") (pin "3") (pinfunction "3_3") (pintype "passive"))
      (node (ref "X1") (pin "4") (pinfunction "4_4") (pintype "passive"))
    )
    (net (code "4") (name "+24V") (class "Default")
      (node (ref "JP3") (pin "1") (pinfunction "1_1") (pintype "passive"))
      (node (ref "R7") (pin "1") (pinfunction "1_1") (pintype "passive"))
    )
    (net (code "5") (name "CAM-UTIL") (class "Default")
      (node (ref "SJ4") (pin "2") (pinfunction "2_2") (pintype "passive"))
      (node (ref "SV1") (pin "13") (pinfunction "13_13") (pintype "passive"))
    )
    (net (code "6") (name "DRIBBLER") (class "Default")
      (node (ref "U1") (pin "44") (pinfunction "PA11/TIM1_CH4/USART1_CTS/CAN1_RX/OTG_FS_DM/EVENTOUT_44") (pintype "bidirectional"))
      (node (ref "X2") (pin "3") (pinfunction "3_3") (pintype "passive"))
    )
    (net (code "7") (name "ESC-L-EMG1") (class "Default")
      (node (ref "TP46") (pin "TP") (pinfunction "PP_TP") (pintype "input"))
      (node (ref "U1") (pin "26") (pinfunction "PB0/TIM1_CH2N/TIM3_CH3/TIM8_CH2N/SPI3_MOSI/I2S3_SD/UART4_CTS/OTG_HS_ULPI_D1/SDIO_D1/EVENTOUT_26") (pintype "bidirectional"))
    )
    (net (code "8") (name "ESC-L-EMG2") (class "Default")
      (node (ref "TP47") (pin "TP") (pinfunction "PP_TP") (pintype "input"))
      (node (ref "U1") (pin "34") (pinfunction "PB13/TIM1_CH1N/SPI2_SCK/I2S2_CK/USART3_CTS/CAN2_TX/OTG_HS_ULPI_D6/EVENTOUT_34") (pintype "bidirectional"))
    )
    (net (code "9") (name "ESC-L-RX") (class "Default")
      (node (ref "TP48") (pin "TP") (pinfunction "PP_TP") (pintype "input"))
      (node (ref "U1") (pin "15") (pinfunction "PA1/TIM2_CH2/TIM5_CH2/USART2_RTS/UART4_RX/QUADSPI_BK1_IO3/SAI2_MCLK_B/EVENTOUT_15") (pintype "bidirectional"))
    )
    (net (code "10") (name "ESC-L-TX") (class "Default")
      (node (ref "TP44") (pin "TP") (pinfunction "PP_TP") (pintype "input"))
      (node (ref "U1") (pin "14") (pinfunction "PA0-WKUP(PA0)TIM2_CH1/TIM2_ETR/TIM5_CH1/TIM8_ETR/USART2_CTS/UART4_TX/EVENTOUT_14") (pintype "bidirectional"))
    )
    (net (code "11") (name "ESC-R-EMG1") (class "Default")
      (node (ref "TP31") (pin "TP") (pinfunction "PP_TP") (pintype "input"))
      (node (ref "U1") (pin "35") (pinfunction "PB14/TIM1_CH2N/TIM8_CH2N/SPI2_MISO/USART3_RTS/TIM12_CH1/OTG_HS_DM/EVENTOUT_35") (pintype "bidirectional"))
    )
    (net (code "12") (name "ESC-R-EMG2") (class "Default")
      (node (ref "TP41") (pin "TP") (pinfunction "PP_TP") (pintype "input"))
      (node (ref "U1") (pin "36") (pinfunction "PB15/RTC_REFIN/TIM1_CH3N/TIM8_CH3N/SPI2_MOSI/I2S2_SD/TIM12_CH2/OTG_HS_DP/EVENTOUT_36") (pintype "bidirectional"))
    )
    (net (code "13") (name "ESC-R-RX") (class "Default")
      (node (ref "TP42") (pin "TP") (pinfunction "PP_TP") (pintype "input"))
      (node (ref "U1") (pin "43") (pinfunction "PA10/TIM1_CH3/USART1_RX/OTG_FS_ID/DCMI_D1/EVENTOUT_43") (pintype "bidirectional"))
    )
    (net (code "14") (name "ESC-R-TX") (class "Default")
      (node (ref "TP29") (pin "TP") (pinfunction "PP_TP") (pintype "input"))
      (node (ref "U1") (pin "42") (pinfunction "PA9/TIM1_CH2/I2C3_SMBA/SPI2_SCK/I2S2_CK/SAI1_SD_B/USART1_TX/DCMI_D0/EVENTOUT_42") (pintype "bidirectional"))
    )
    (net (code "15") (name "GND") (class "Default")
      (node (ref "C1") (pin "2") (pinfunction "2_2") (pintype "passive"))
      (node (ref "C10") (pin "2") (pinfunction "2_2") (pintype "passive"))
      (node (ref "C11") (pin "2") (pinfunction "2_2") (pintype "passive"))
      (node (ref "C12") (pin "2") (pinfunction "2_2") (pintype "passive"))
      (node (ref "C13") (pin "2") (pinfunction "2_2") (pintype "passive"))
      (node (ref "C14") (pin "-") (pinfunction "-_-") (pintype "passive"))
      (node (ref "C15") (pin "2") (pinfunction "2_2") (pintype "passive"))
      (node (ref "C16") (pin "2") (pinfunction "2_2") (pintype "passive"))
      (node (ref "C2") (pin "2") (pinfunction "2_2") (pintype "passive"))
      (node (ref "C3") (pin "P$1") (pinfunction "-_P$1") (pintype "passive"))
      (node (ref "C4") (pin "P$1") (pinfunction "-_P$1") (pintype "passive"))
      (node (ref "C5") (pin "-") (pinfunction "-_-") (pintype "passive"))
      (node (ref "C6") (pin "2") (pinfunction "2_2") (pintype "passive"))
      (node (ref "C7") (pin "2") (pinfunction "2_2") (pintype "passive"))
      (node (ref "C8") (pin "2") (pinfunction "2_2") (pintype "passive"))
      (node (ref "C9") (pin "2") (pinfunction "2_2") (pintype "passive"))
      (node (ref "IC2") (pin "GND") (pinfunction "GND_GND") (pintype "input"))
      (node (ref "JP2") (pin "1") (pinfunction "1_1") (pintype "passive"))
      (node (ref "JP4") (pin "1") (pinfunction "1_1") (pintype "passive"))
      (node (ref "OK1") (pin "2") (pinfunction "C_2") (pintype "passive"))
      (node (ref "OK1") (pin "4") (pinfunction "C_4") (pintype "passive"))
      (node (ref "Q1") (pin "3") (pinfunction "S_3") (pintype "passive"))
      (node (ref "R11") (pin "1") (pinfunction "1_1") (pintype "passive"))
      (node (ref "R13") (pin "1") (pinfunction "1_1") (pintype "passive"))
      (node (ref "R15") (pin "1") (pinfunction "1_1") (pintype "passive"))
      (node (ref "R17") (pin "1") (pinfunction "A_1") (pintype "passive"))
      (node (ref "R2") (pin "1") (pinfunction "1_1") (pintype "passive"))
      (node (ref "R3") (pin "1") (pinfunction "1_1") (pintype "passive"))
      (node (ref "R8") (pin "2") (pinfunction "2_2") (pintype "passive"))
      (node (ref "R9") (pin "1") (pinfunction "1_1") (pintype "passive"))
      (node (ref "REG1") (pin "4") (pinfunction "GND_4") (pintype "passive"))
      (node (ref "SJ1") (pin "2") (pinfunction "2_2") (pintype "passive"))
      (node (ref "SJ2") (pin "2") (pinfunction "2_2") (pintype "passive"))
      (node (ref "SJ3") (pin "2") (pinfunction "2_2") (pintype "passive"))
      (node (ref "SV1") (pin "3") (pinfunction "3_3") (pintype "passive"))
      (node (ref "TP10") (pin "TP-2") (pinfunction "TP_TP-2") (pintype "input"))
      (node (ref "TP14") (pin "TP") (pinfunction "PP_TP") (pintype "input"))
      (node (ref "TP20") (pin "TP-2") (pinfunction "TP_TP-2") (pintype "input"))
      (node (ref "TP21") (pin "TP-2") (pinfunction "TP_TP-2") (pintype "input"))
      (node (ref "TP22") (pin "TP-2") (pinfunction "TP_TP-2") (pintype "input"))
      (node (ref "TP24") (pin "TP") (pinfunction "PP_TP") (pintype "input"))
      (node (ref "TP30") (pin "TP") (pinfunction "PP_TP") (pintype "input"))
      (node (ref "TP35") (pin "TP") (pinfunction "PP_TP") (pintype "input"))
      (node (ref "TP4") (pin "TP") (pinfunction "PP_TP") (pintype "input"))
      (node (ref "TP45") (pin "TP") (pinfunction "PP_TP") (pintype "input"))
      (node (ref "U$1") (pin "P$20") (pinfunction "P$20_P$20") (pintype "bidirectional"))
      (node (ref "U$1") (pin "P$22") (pinfunction "P$22_P$22") (pintype "bidirectional"))
      (node (ref "U$1") (pin "P$25") (pinfunction "P$25_P$25") (pintype "bidirectional"))
      (node (ref "U$1") (pin "P$28") (pinfunction "P$28_P$28") (pintype "bidirectional"))
      (node (ref "U$2") (pin "P$2") (pinfunction "2_P$2") (pintype "passive"))
      (node (ref "U1") (pin "12") (pinfunction "VSSA/VREF-_12") (pintype "power_in"))
      (node (ref "U1") (pin "18") (pinfunction "VSS_18") (pintype "power_in"))
      (node (ref "U1") (pin "31") (pinfunction "VSS_31") (pintype "power_in"))
      (node (ref "U1") (pin "47") (pinfunction "VSS_47") (pintype "power_in"))
      (node (ref "U1") (pin "63") (pinfunction "VSS_63") (pintype "power_in"))
      (node (ref "U2") (pin "15") (pinfunction "VSS_15") (pintype "power_in"))
      (node (ref "U3") (pin "15") (pinfunction "VSS_15") (pintype "power_in"))
      (node (ref "U4") (pin "15") (pinfunction "VSS_15") (pintype "power_in"))
      (node (ref "U5") (pin "15") (pinfunction "VSS_15") (pintype "power_in"))
      (node (ref "X1") (pin "1") (pinfunction "1_1") (pintype "passive"))
      (node (ref "X1") (pin "2") (pinfunction "2_2") (pintype "passive"))
      (node (ref "X2") (pin "1") (pinfunction "1_1") (pintype "passive"))
    )
    (net (code "16") (name "L010-NRST-B") (class "Default")
      (node (ref "C12") (pin "1") (pinfunction "1_1") (pintype "passive"))
      (node (ref "R16") (pin "1") (pinfunction "1_1") (pintype "passive"))
      (node (ref "U5") (pin "4") (pinfunction "~{RST}_4") (pintype "input"))
    )
    (net (code "17") (name "L010-NRST-F") (class "Default")
      (node (ref "C11") (pin "1") (pinfunction "1_1") (pintype "passive"))
      (node (ref "R14") (pin "1") (pinfunction "1_1") (pintype "passive"))
      (node (ref "U4") (pin "4") (pinfunction "~{RST}_4") (pintype "input"))
    )
    (net (code "18") (name "L010-NRST-L") (class "Default")
      (node (ref "C9") (pin "1") (pinfunction "1_1") (pintype "passive"))
      (node (ref "R10") (pin "1") (pinfunction "1_1") (pintype "passive"))
      (node (ref "U2") (pin "4") (pinfunction "~{RST}_4") (pintype "input"))
    )
    (net (code "19") (name "L010-NRST-R") (class "Default")
      (node (ref "C10") (pin "1") (pinfunction "1_1") (pintype "passive"))
      (node (ref "R12") (pin "1") (pinfunction "1_1") (pintype "passive"))
      (node (ref "U3") (pin "4") (pinfunction "~{RST}_4") (pintype "input"))
    )
    (net (code "20") (name "L010-SWCLK-B") (class "Default")
      (node (ref "U5") (pin "20") (pinfunction "PA14_20") (pintype "bidirectional"))
    )
    (net (code "21") (name "L010-SWCLK-F") (class "Default")
      (node (ref "U4") (pin "20") (pinfunction "PA14_20") (pintype "bidirectional"))
    )
    (net (code "22") (name "L010-SWCLK-L") (class "Default")
      (node (ref "U2") (pin "20") (pinfunction "PA14_20") (pintype "bidirectional"))
    )
    (net (code "23") (name "L010-SWCLK-R") (class "Default")
      (node (ref "U3") (pin "20") (pinfunction "PA14_20") (pintype "bidirectional"))
    )
    (net (code "24") (name "L010-SWDIO-B") (class "Default")
      (node (ref "U5") (pin "19") (pinfunction "PA13_19") (pintype "bidirectional"))
    )
    (net (code "25") (name "L010-SWDIO-F") (class "Default")
      (node (ref "U4") (pin "19") (pinfunction "PA13_19") (pintype "bidirectional"))
    )
    (net (code "26") (name "L010-SWDIO-L") (class "Default")
      (node (ref "U2") (pin "19") (pinfunction "PA13_19") (pintype "bidirectional"))
    )
    (net (code "27") (name "L010-SWDIO-R") (class "Default")
      (node (ref "U3") (pin "19") (pinfunction "PA13_19") (pintype "bidirectional"))
    )
    (net (code "28") (name "LED-B") (class "Default")
      (node (ref "R23") (pin "1") (pinfunction "1_1") (pintype "passive"))
      (node (ref "T3") (pin "2") (pinfunction "S_2") (pintype "passive"))
      (node (ref "U1") (pin "9") (pinfunction "PC1/SPI3_MOSI/I2S3_SD/SAI1_SD_A/SPI2_MOSI/I2S2_SD/EVENTOUT_9") (pintype "bidirectional"))
    )
    (net (code "29") (name "LED-B-5V") (class "Default")
      (node (ref "R24") (pin "1") (pinfunction "1_1") (pintype "passive"))
      (node (ref "T3") (pin "1") (pinfunction "D_1") (pintype "passive"))
      (node (ref "U$2") (pin "P$5") (pinfunction "5_P$5") (pintype "passive"))
    )
    (net (code "30") (name "LED-F") (class "Default")
      (node (ref "R21") (pin "1") (pinfunction "1_1") (pintype "passive"))
      (node (ref "T2") (pin "2") (pinfunction "S_2") (pintype "passive"))
      (node (ref "U1") (pin "59") (pinfunction "PB7/TIM4_CH2/I2C1_SDA/USART1_RX/SPDIFRX_IN0/FMC_NL/DCMI_VSYNC/EVENTOUT_59") (pintype "bidirectional"))
    )
    (net (code "31") (name "LED-F-5V") (class "Default")
      (node (ref "R22") (pin "1") (pinfunction "1_1") (pintype "passive"))
      (node (ref "T2") (pin "1") (pinfunction "D_1") (pintype "passive"))
      (node (ref "TP32") (pin "TP") (pinfunction "PP_TP") (pintype "input"))
    )
    (net (code "32") (name "LED-L") (class "Default")
      (node (ref "R25") (pin "1") (pinfunction "1_1") (pintype "passive"))
      (node (ref "T4") (pin "2") (pinfunction "S_2") (pintype "passive"))
      (node (ref "U1") (pin "50") (pinfunction "PA15/JTDI/TIM2_CH1/TIM2_ETR/HDMI_CEC/SPI1_NSS/I2S1_WS/SPI3_NSS/I2S3_WS/UART4_RTS/EVENTOUT_50") (pintype "bidirectional"))
    )
    (net (code "33") (name "LED-L-5V") (class "Default")
      (node (ref "R26") (pin "1") (pinfunction "1_1") (pintype "passive"))
      (node (ref "T4") (pin "1") (pinfunction "D_1") (pintype "passive"))
      (node (ref "TP11") (pin "TP") (pinfunction "PP_TP") (pintype "input"))
    )
    (net (code "34") (name "LED-R") (class "Default")
      (node (ref "R27") (pin "1") (pinfunction "1_1") (pintype "passive"))
      (node (ref "T5") (pin "2") (pinfunction "S_2") (pintype "passive"))
      (node (ref "U1") (pin "27") (pinfunction "PB1/TIM1_CH3N/TIM3_CH4/TIM8_CH3N/OTG_HS_ULPI_D2/SDIO_D2/EVENTOUT_27") (pintype "bidirectional"))
    )
    (net (code "35") (name "LED-R-5V") (class "Default")
      (node (ref "R28") (pin "1") (pinfunction "1_1") (pintype "passive"))
      (node (ref "T5") (pin "1") (pinfunction "D_1") (pintype "passive"))
      (node (ref "TP1") (pin "TP") (pinfunction "PP_TP") (pintype "input"))
    )
    (net (code "36") (name "MISO") (class "Default")
      (node (ref "SV1") (pin "5") (pinfunction "5_5") (pintype "passive"))
      (node (ref "U1") (pin "22") (pinfunction "PA6/TIM1_BKIN/TIM3_CH1/TIM8_BKIN/SPI1_MISO/I2S2_MCK/TIM13_CH1/DCMI_PIXCLK/EVENTOUT_22") (pintype "bidirectional"))
    )
    (net (code "37") (name "MOSI") (class "Default")
      (node (ref "SV1") (pin "7") (pinfunction "7_7") (pintype "passive"))
      (node (ref "U1") (pin "23") (pinfunction "PA7/TIM1_CH1N/TIM3_CH2/TIM8_CH1N/SPI1_MOSI/I2S1_SD/TIM14_CH1/FMC_SDNWE/EVENTOUT_23") (pintype "bidirectional"))
    )
    (net (code "38") (name "MUX-B") (class "Default")
      (node (ref "U$2") (pin "P$3") (pinfunction "3_P$3") (pintype "passive"))
      (node (ref "U5") (pin "7") (pinfunction "PA1_7") (pintype "bidirectional"))
    )
    (net (code "39") (name "MUX-F") (class "Default")
      (node (ref "TP34") (pin "TP") (pinfunction "PP_TP") (pintype "input"))
      (node (ref "U4") (pin "7") (pinfunction "PA1_7") (pintype "bidirectional"))
    )
    (net (code "40") (name "MUX-L") (class "Default")
      (node (ref "TP13") (pin "TP") (pinfunction "PP_TP") (pintype "input"))
      (node (ref "U2") (pin "7") (pinfunction "PA1_7") (pintype "bidirectional"))
    )
    (net (code "41") (name "MUX-R") (class "Default")
      (node (ref "TP3") (pin "TP") (pinfunction "PP_TP") (pintype "input"))
      (node (ref "U3") (pin "7") (pinfunction "PA1_7") (pintype "bidirectional"))
    )
    (net (code "42") (name "NEOPIXEL") (class "Default")
      (node (ref "R19") (pin "1") (pinfunction "1_1") (pintype "passive"))
      (node (ref "T1") (pin "2") (pinfunction "S_2") (pintype "passive"))
      (node (ref "U1") (pin "58") (pinfunction "PB6/TIM4_CH1/HDMI_CEC/I2C1_SCL/USART1_TX/CAN2_TX/QUADSPI_BK1_NCS/FMC_SDNE1/DCMI_D5/EVENTOUT_58") (pintype "bidirectional"))
    )
    (net (code "43") (name "NEOPIXEL-5V") (class "Default")
      (node (ref "R20") (pin "1") (pinfunction "1_1") (pintype "passive"))
      (node (ref "SV1") (pin "10") (pinfunction "10_10") (pintype "passive"))
      (node (ref "T1") (pin "1") (pinfunction "D_1") (pintype "passive"))
    )
    (net (code "44") (name "NRST") (class "Default")
      (node (ref "C1") (pin "1") (pinfunction "1_1") (pintype "passive"))
      (node (ref "SV1") (pin "8") (pinfunction "8_8") (pintype "passive"))
      (node (ref "U1") (pin "7") (pinfunction "NRST_7") (pintype "bidirectional"))
    )
    (net (code "45") (name "Net-(C3-+)") (class "Default")
      (node (ref "C3") (pin "P$2") (pinfunction "+_P$2") (pintype "passive"))
      (node (ref "C4") (pin "P$2") (pinfunction "+_P$2") (pintype "passive"))
      (node (ref "CN1") (pin "1") (pinfunction "1_1") (pintype "passive"))
      (node (ref "D1") (pin "C") (pinfunction "C_C") (pintype "passive"))
      (node (ref "OK1") (pin "6") (pinfunction "COL_6") (pintype "passive"))
      (node (ref "S1") (pin "3") (pinfunction "P_3") (pintype "passive"))
      (node (ref "S1") (pin "4") (pinfunction "P1_4") (pintype "passive"))
    )
    (net (code "46") (name "Net-(OK1A-A)") (class "Default")
      (node (ref "OK1") (pin "1") (pinfunction "A_1") (pintype "passive"))
      (node (ref "R5") (pin "1") (pinfunction "1_1") (pintype "passive"))
    )
    (net (code "47") (name "Net-(OK1A-COL)") (class "Default")
      (node (ref "OK1") (pin "8") (pinfunction "COL_8") (pintype "passive"))
      (node (ref "Q2") (pin "2") (pinfunction "S_2") (pintype "passive"))
      (node (ref "R1") (pin "2") (pinfunction "2_2") (pintype "passive"))
      (node (ref "R7") (pin "2") (pinfunction "2_2") (pintype "passive"))
    )
    (net (code "48") (name "Net-(OK1A-EMIT)") (class "Default")
      (node (ref "OK1") (pin "7") (pinfunction "EMIT_7") (pintype "passive"))
      (node (ref "Q2") (pin "1") (pinfunction "G_1") (pintype "passive"))
      (node (ref "R1") (pin "1") (pinfunction "1_1") (pintype "passive"))
      (node (ref "R2") (pin "2") (pinfunction "2_2") (pintype "passive"))
    )
    (net (code "49") (name "Net-(OK1B-A)") (class "Default")
      (node (ref "OK1") (pin "3") (pinfunction "A_3") (pintype "passive"))
      (node (ref "R6") (pin "1") (pinfunction "1_1") (pintype "passive"))
    )
    (net (code "50") (name "Net-(OK1B-EMIT)") (class "Default")
      (node (ref "OK1") (pin "5") (pinfunction "EMIT_5") (pintype "passive"))
      (node (ref "R4") (pin "2") (pinfunction "2_2") (pintype "passive"))
      (node (ref "S1") (pin "1") (pinfunction "S_1") (pintype "passive"))
      (node (ref "S1") (pin "2") (pinfunction "S1_2") (pintype "passive"))
    )
    (net (code "51") (name "Net-(Q1-D)") (class "Default")
      (node (ref "CN1") (pin "2") (pinfunction "2_2") (pintype "passive"))
      (node (ref "Q1") (pin "4") (pinfunction "D_4") (pintype "passive"))
    )
    (net (code "52") (name "Net-(Q1-G)") (class "Default")
      (node (ref "Q1") (pin "1") (pinfunction "G_1") (pintype "passive"))
      (node (ref "R3") (pin "2") (pinfunction "2_2") (pintype "passive"))
      (node (ref "R4") (pin "1") (pinfunction "1_1") (pintype "passive"))
    )
    (net (code "53") (name "Net-(Q2-D)") (class "Default")
      (node (ref "D1") (pin "A") (pinfunction "A_A") (pintype "passive"))
      (node (ref "Q2") (pin "3") (pinfunction "D_3") (pintype "passive"))
    )
    (net (code "54") (name "Net-(SJ1-Pad1)") (class "Default")
      (node (ref "SJ1") (pin "1") (pinfunction "1_1") (pintype "passive"))
      (node (ref "U$1") (pin "P$12") (pinfunction "P$12_P$12") (pintype "bidirectional"))
    )
    (net (code "55") (name "Net-(SJ2-Pad1)") (class "Default")
      (node (ref "SJ2") (pin "1") (pinfunction "1_1") (pintype "passive"))
      (node (ref "U$1") (pin "P$26") (pinfunction "P$26_P$26") (pintype "bidirectional"))
    )
    (net (code "56") (name "Net-(SJ3-Pad1)") (class "Default")
      (node (ref "SJ3") (pin "1") (pinfunction "1_1") (pintype "passive"))
      (node (ref "U$1") (pin "P$27") (pinfunction "P$27_P$27") (pintype "bidirectional"))
    )
    (net (code "57") (name "Net-(U1-BOOT0)") (class "Default")
      (node (ref "R8") (pin "1") (pinfunction "1_1") (pintype "passive"))
      (node (ref "U1") (pin "60") (pinfunction "BOOT0_60") (pintype "input"))
    )
    (net (code "58") (name "Net-(U1-VCAP_1)") (class "Default")
      (node (ref "C5") (pin "+") (pinfunction "+_+") (pintype "passive"))
      (node (ref "U1") (pin "30") (pinfunction "VCAP_1_30") (pintype "power_in"))
    )
    (net (code "59") (name "Net-(U2-PB9-BOOT0)") (class "Default")
      (node (ref "R9") (pin "2") (pinfunction "2_2") (pintype "passive"))
      (node (ref "U2") (pin "1") (pinfunction "PB9-BOOT0_1") (pintype "input"))
    )
    (net (code "60") (name "Net-(U3-PB9-BOOT0)") (class "Default")
      (node (ref "R11") (pin "2") (pinfunction "2_2") (pintype "passive"))
      (node (ref "U3") (pin "1") (pinfunction "PB9-BOOT0_1") (pintype "input"))
    )
    (net (code "61") (name "Net-(U4-PB9-BOOT0)") (class "Default")
      (node (ref "R13") (pin "2") (pinfunction "2_2") (pintype "passive"))
      (node (ref "U4") (pin "1") (pinfunction "PB9-BOOT0_1") (pintype "input"))
    )
    (net (code "62") (name "Net-(U5-PB9-BOOT0)") (class "Default")
      (node (ref "R15") (pin "2") (pinfunction "2_2") (pintype "passive"))
      (node (ref "U5") (pin "1") (pinfunction "PB9-BOOT0_1") (pintype "input"))
    )
    (net (code "63") (name "RADIO-IN1") (class "Default")
      (node (ref "U$1") (pin "P$7") (pinfunction "P$7_P$7") (pintype "bidirectional"))
      (node (ref "U1") (pin "10") (pinfunction "PC2/SPI2_MISO/OTG_HS_ULPI_DIR/FMC_SDNE0/EVENTOUT_10") (pintype "bidirectional"))
    )
    (net (code "64") (name "RADIO-IN2") (class "Default")
      (node (ref "U$1") (pin "P$1") (pinfunction "P$1_P$1") (pintype "bidirectional"))
      (node (ref "U1") (pin "24") (pinfunction "PC4/I2S1_MCK/SPDIFRX_IN2/FMC_SDNE0/EVENTOUT_24") (pintype "bidirectional"))
    )
    (net (code "65") (name "RADIO-IN3") (class "Default")
      (node (ref "U$1") (pin "P$3") (pinfunction "P$3_P$3") (pintype "bidirectional"))
      (node (ref "U1") (pin "2") (pinfunction "PC13/EVENTOUT_2") (pintype "bidirectional"))
    )
    (net (code "66") (name "RADIO-OUT1") (class "Default")
      (node (ref "U$1") (pin "P$23") (pinfunction "P$23_P$23") (pintype "bidirectional"))
      (node (ref "U1") (pin "11") (pinfunction "PC3/SPI2_MOSI/I2S2_SD/OTG_HS_ULPI_NXT/FMC_SDCKE0/EVENTOUT_11") (pintype "bidirectional"))
    )
    (net (code "67") (name "RADIO-OUT2") (class "Default")
      (node (ref "U$1") (pin "P$24") (pinfunction "P$24_P$24") (pintype "bidirectional"))
      (node (ref "U1") (pin "25") (pinfunction "PC5/USART3_RX/SPDIFRX_IN3/FMC_SDCKE0/EVENTOUT_25") (pintype "bidirectional"))
    )
    (net (code "68") (name "RADIO-OUT3") (class "Default")
      (node (ref "U$1") (pin "P$13") (pinfunction "P$13_P$13") (pintype "bidirectional"))
      (node (ref "U1") (pin "40") (pinfunction "PC9/MCO2/TIM3_CH4/TIM8_CH4/I2C3_SDA/I2S_CKIN/UART5_CTS/QUADSPI_BK1_IO0/SDIO_D1/DCMI_D3/EVENTOUT_40") (pintype "bidirectional"))
    )
    (net (code "69") (name "RADIO-RX") (class "Default")
      (node (ref "U$1") (pin "P$8") (pinfunction "P$8_P$8") (pintype "bidirectional"))
      (node (ref "U1") (pin "54") (pinfunction "PD2/TIM3_ETR/UART5_RX/SDIO_CMD/DCMI_D11/EVENTOUT_54") (pintype "bidirectional"))
    )
    (net (code "70") (name "RADIO-TX") (class "Default")
      (node (ref "U$1") (pin "P$9") (pinfunction "P$9_P$9") (pintype "bidirectional"))
      (node (ref "U1") (pin "53") (pinfunction "PC12/I2C2_SDA/SPI3_MOSI/I2S3_SD/USART3_CK/UART5_TX/SDIO_CK/DCMI_D9/EVENTOUT_53") (pintype "bidirectional"))
    )
    (net (code "71") (name "RX-CAM") (class "Default")
      (node (ref "SV1") (pin "19") (pinfunction "19_19") (pintype "passive"))
      (node (ref "U1") (pin "38") (pinfunction "PC7/TIM3_CH2/TIM8_CH2/FMPI2C1_SDA/SPI2_SCK/I2S2_CK/I2S3_MCK/SPDIFRX_IN1/USART6_RX/SDIO_D7/DCMI_D1/EVENTOUT_38") (pintype "bidirectional"))
    )
    (net (code "72") (name "RX-PC") (class "Default")
      (node (ref "SV1") (pin "16") (pinfunction "16_16") (pintype "passive"))
      (node (ref "U1") (pin "17") (pinfunction "PA3/TIM2_CH4/TIM5_CH4/TIM9_CH2/SAI1_FS_A/USART2_RX/OTG_HS_ULPI_D0/EVENTOUT_17") (pintype "bidirectional"))
    )
    (net (code "73") (name "S0-B") (class "Default")
      (node (ref "JP6") (pin "2") (pinfunction "2_2") (pintype "passive"))
      (node (ref "U5") (pin "10") (pinfunction "PA4_10") (pintype "bidirectional"))
    )
    (net (code "74") (name "S0-F") (class "Default")
      (node (ref "TP39") (pin "TP") (pinfunction "PP_TP") (pintype "input"))
      (node (ref "U4") (pin "10") (pinfunction "PA4_10") (pintype "bidirectional"))
    )
    (net (code "75") (name "S0-L") (class "Default")
      (node (ref "TP18") (pin "TP") (pinfunction "PP_TP") (pintype "input"))
      (node (ref "U2") (pin "10") (pinfunction "PA4_10") (pintype "bidirectional"))
    )
    (net (code "76") (name "S0-R") (class "Default")
      (node (ref "TP8") (pin "TP") (pinfunction "PP_TP") (pintype "input"))
      (node (ref "U3") (pin "10") (pinfunction "PA4_10") (pintype "bidirectional"))
    )
    (net (code "77") (name "S1-B") (class "Default")
      (node (ref "JP5") (pin "1") (pinfunction "1_1") (pintype "passive"))
      (node (ref "U5") (pin "11") (pinfunction "PA5_11") (pintype "bidirectional"))
    )
    (net (code "78") (name "S1-F") (class "Default")
      (node (ref "TP38") (pin "TP") (pinfunction "PP_TP") (pintype "input"))
      (node (ref "U4") (pin "11") (pinfunction "PA5_11") (pintype "bidirectional"))
    )
    (net (code "79") (name "S1-L") (class "Default")
      (node (ref "TP17") (pin "TP") (pinfunction "PP_TP") (pintype "input"))
      (node (ref "U2") (pin "11") (pinfunction "PA5_11") (pintype "bidirectional"))
    )
    (net (code "80") (name "S1-R") (class "Default")
      (node (ref "TP7") (pin "TP") (pinfunction "PP_TP") (pintype "input"))
      (node (ref "U3") (pin "11") (pinfunction "PA5_11") (pintype "bidirectional"))
    )
    (net (code "81") (name "S2-B") (class "Default")
      (node (ref "JP5") (pin "2") (pinfunction "2_2") (pintype "passive"))
      (node (ref "U5") (pin "12") (pinfunction "PA6_12") (pintype "bidirectional"))
    )
    (net (code "82") (name "S2-F") (class "Default")
      (node (ref "TP37") (pin "TP") (pinfunction "PP_TP") (pintype "input"))
      (node (ref "U4") (pin "12") (pinfunction "PA6_12") (pintype "bidirectional"))
    )
    (net (code "83") (name "S2-L") (class "Default")
      (node (ref "TP16") (pin "TP") (pinfunction "PP_TP") (pintype "input"))
      (node (ref "U2") (pin "12") (pinfunction "PA6_12") (pintype "bidirectional"))
    )
    (net (code "84") (name "S2-R") (class "Default")
      (node (ref "TP6") (pin "TP") (pinfunction "PP_TP") (pintype "input"))
      (node (ref "U3") (pin "12") (pinfunction "PA6_12") (pintype "bidirectional"))
    )
    (net (code "85") (name "S3-B") (class "Default")
      (node (ref "U$2") (pin "P$1") (pinfunction "1_P$1") (pintype "passive"))
      (node (ref "U5") (pin "13") (pinfunction "PA7_13") (pintype "bidirectional"))
    )
    (net (code "86") (name "S3-F") (class "Default")
      (node (ref "TP36") (pin "TP") (pinfunction "PP_TP") (pintype "input"))
      (node (ref "U4") (pin "13") (pinfunction "PA7_13") (pintype "bidirectional"))
    )
    (net (code "87") (name "S3-L") (class "Default")
      (node (ref "TP15") (pin "TP") (pinfunction "PP_TP") (pintype "input"))
      (node (ref "U2") (pin "13") (pinfunction "PA7_13") (pintype "bidirectional"))
    )
    (net (code "88") (name "S3-R") (class "Default")
      (node (ref "TP5") (pin "TP") (pinfunction "PP_TP") (pintype "input"))
      (node (ref "U3") (pin "13") (pinfunction "PA7_13") (pintype "bidirectional"))
    )
    (net (code "89") (name "SCK") (class "Default")
      (node (ref "SV1") (pin "9") (pinfunction "9_9") (pintype "passive"))
      (node (ref "U1") (pin "21") (pinfunction "PA5/TIM2_CH1/TIM2_ETR/TIM8_CH1N/SPI1_SCK/I2S1_CK/OTG_HS_ULPI_CK/EVENTOUT_21") (pintype "bidirectional"))
    )
    (net (code "90") (name "SCL") (class "Default")
      (node (ref "SV1") (pin "14") (pinfunction "14_14") (pintype "passive"))
      (node (ref "U1") (pin "61") (pinfunction "PB8/TIM2_CH1/TIM2_ETR/TIM4_CH3/TIM10_CH1/I2C1_SCL/CAN1_RX/SDIO_D4/DCMI_D6/EVENTOUT_61") (pintype "bidirectional"))
      (node (ref "U2") (pin "17") (pinfunction "PA9_17") (pintype "bidirectional"))
      (node (ref "U3") (pin "17") (pinfunction "PA9_17") (pintype "bidirectional"))
      (node (ref "U4") (pin "17") (pinfunction "PA9_17") (pintype "bidirectional"))
      (node (ref "U5") (pin "17") (pinfunction "PA9_17") (pintype "bidirectional"))
    )
    (net (code "91") (name "SDA") (class "Default")
      (node (ref "SV1") (pin "12") (pinfunction "12_12") (pintype "passive"))
      (node (ref "U1") (pin "62") (pinfunction "PB9/TIM2_CH2/TIM4_CH4/TIM11_CH1/I2C1_SDA/SPI2_NSS/I2S2_WS/SAI1_FS_B/CAN1_TX/SDIO_D5/DCMI_D7/EVENTOUT_62") (pintype "bidirectional"))
      (node (ref "U2") (pin "18") (pinfunction "PA10_18") (pintype "bidirectional"))
      (node (ref "U3") (pin "18") (pinfunction "PA10_18") (pintype "bidirectional"))
      (node (ref "U4") (pin "18") (pinfunction "PA10_18") (pintype "bidirectional"))
      (node (ref "U5") (pin "18") (pinfunction "PA10_18") (pintype "bidirectional"))
    )
    (net (code "92") (name "SOLENOID") (class "Default")
      (node (ref "R5") (pin "2") (pinfunction "2_2") (pintype "passive"))
      (node (ref "R6") (pin "2") (pinfunction "2_2") (pintype "passive"))
      (node (ref "U1") (pin "20") (pinfunction "PA4/SPI1_NSS/I2S1_WS/SPI3_NSS/I2S3_WS/USART2_CK/OTG_HS_SOF/DCMI_HSYNC/EVENTOUT_20") (pintype "bidirectional"))
    )
    (net (code "93") (name "SPK-BUSY") (class "Default")
      (node (ref "TP27") (pin "TP") (pinfunction "PP_TP") (pintype "input"))
      (node (ref "U1") (pin "39") (pinfunction "PC8/TRACED0/TIM3_CH3/TIM8_CH3/UART5_RTS/USART6_CK/SDIO_D0/DCMI_D2/EVENTOUT_39") (pintype "bidirectional"))
    )
    (net (code "94") (name "SPK-RX") (class "Default")
      (node (ref "TP26") (pin "TP") (pinfunction "PP_TP") (pintype "input"))
      (node (ref "U1") (pin "52") (pinfunction "PC11/SPI3_MISO/USART3_RX/UART4_RX/QUADSPI_BK2_NCS/SDIO_D3/DCMI_D4/EVENTOUT_52") (pintype "bidirectional"))
    )
    (net (code "95") (name "SPK-TX") (class "Default")
      (node (ref "TP25") (pin "TP") (pinfunction "PP_TP") (pintype "input"))
      (node (ref "U1") (pin "51") (pinfunction "PC10/SPI3_SCK/I2S3_CK/USART3_TX/UART4_TX/QUADSPI_BK1_IO1/SDIO_D2/DCMI_D8/EVENTOUT_51") (pintype "bidirectional"))
    )
    (net (code "96") (name "SS-CAM") (class "Default")
      (node (ref "SJ4") (pin "1") (pinfunction "1_1") (pintype "passive"))
      (node (ref "U1") (pin "56") (pinfunction "PB4(NJTRST)/NJTRST/TIM3_CH1/I2C3_SDA/SPI1_MISO/SPI3_MISO/SPI2_NSS/I2S2_WS/EVENTOUT_56") (pintype "bidirectional"))
    )
    (net (code "97") (name "SS1") (class "Default")
      (node (ref "SV1") (pin "11") (pinfunction "11_11") (pintype "passive"))
      (node (ref "U1") (pin "57") (pinfunction "PB5/TIM3_CH2/I2C1_SMBA/SPI1_MOSI/I2S1_SD/SPI3_MOSI/I2S3_SD/CAN2_RX/OTG_HS_ULPI_D7/FMC_SDCKE1/DCMI_D10/EVENTOUT_57") (pintype "bidirectional"))
    )
    (net (code "98") (name "SWCLK") (class "Default")
      (node (ref "SV1") (pin "4") (pinfunction "4_4") (pintype "passive"))
      (node (ref "U1") (pin "49") (pinfunction "PA14/JTCK-SWCLK/EVENTOUT_49") (pintype "bidirectional"))
    )
    (net (code "99") (name "SWDIO") (class "Default")
      (node (ref "SV1") (pin "6") (pinfunction "6_6") (pintype "passive"))
      (node (ref "U1") (pin "46") (pinfunction "PA13/JTMS-SWDIO/EVENTOUT_46") (pintype "bidirectional"))
    )
    (net (code "100") (name "SWO") (class "Default")
      (node (ref "SV1") (pin "17") (pinfunction "17_17") (pintype "passive"))
      (node (ref "U1") (pin "55") (pinfunction "PB3(JTDO/TRACESWO)/JTDO/TRACESWO/TIM2_CH2/I2C2_SDA/SPI1_SCK/I2S1_CK/SPI3_SCK/I2S3_CK/EVENTOUT_55") (pintype "bidirectional"))
    )
    (net (code "101") (name "TX-CAM") (class "Default")
      (node (ref "SJ4") (pin "3") (pinfunction "3_3") (pintype "passive"))
      (node (ref "U1") (pin "37") (pinfunction "PC6/TIM3_CH1/TIM8_CH1/FMPI2C1_SCL/I2S2_MCK/USART6_TX/SDIO_D6/DCMI_D0/EVENTOUT_37") (pintype "bidirectional"))
    )
    (net (code "102") (name "TX-PC") (class "Default")
      (node (ref "SV1") (pin "18") (pinfunction "18_18") (pintype "passive"))
      (node (ref "U1") (pin "16") (pinfunction "PA2/TIM2_CH3/TIM5_CH3/TIM9_CH1/USART2_TX/SAI2_SCK_B/EVENTOUT_16") (pintype "bidirectional"))
    )
    (net (code "103") (name "UI") (class "Default")
      (node (ref "SV1") (pin "20") (pinfunction "20_20") (pintype "passive"))
      (node (ref "U1") (pin "41") (pinfunction "PA8/MCO1/TIM1_CH1/I2C3_SCL/USART1_CK/OTG_FS_SOF/EVENTOUT_41") (pintype "bidirectional"))
    )
    (net (code "104") (name "VOLTAGE") (class "Default")
      (node (ref "R17") (pin "2") (pinfunction "S_2") (pintype "passive"))
      (node (ref "R18") (pin "1") (pinfunction "1_1") (pintype "passive"))
      (node (ref "U1") (pin "8") (pinfunction "PC0/SAI1_MCLK_B/OTG_HS_ULPI_STP/FMC_SDNWE/EVENTOUT_8") (pintype "bidirectional"))
    )
    (net (code "105") (name "unconnected-(R17-E-Pad3)") (class "Default")
      (node (ref "R17") (pin "3") (pinfunction "E_3") (pintype "passive"))
    )
    (net (code "106") (name "unconnected-(U$1-PadP$2)") (class "Default")
      (node (ref "U$1") (pin "P$2") (pinfunction "P$2_P$2") (pintype "bidirectional"))
    )
    (net (code "107") (name "unconnected-(U$1-PadP$4)") (class "Default")
      (node (ref "U$1") (pin "P$4") (pinfunction "P$4_P$4") (pintype "bidirectional"))
    )
    (net (code "108") (name "unconnected-(U$1-PadP$6)") (class "Default")
      (node (ref "U$1") (pin "P$6") (pinfunction "P$6_P$6") (pintype "bidirectional"))
    )
    (net (code "109") (name "unconnected-(U$1-PadP$10)") (class "Default")
      (node (ref "U$1") (pin "P$10") (pinfunction "P$10_P$10") (pintype "bidirectional"))
    )
    (net (code "110") (name "unconnected-(U$1-PadP$11)") (class "Default")
      (node (ref "U$1") (pin "P$11") (pinfunction "P$11_P$11") (pintype "bidirectional"))
    )
    (net (code "111") (name "unconnected-(U$1-PadP$14)") (class "Default")
      (node (ref "U$1") (pin "P$14") (pinfunction "P$14_P$14") (pintype "bidirectional"))
    )
    (net (code "112") (name "unconnected-(U$1-PadP$15)") (class "Default")
      (node (ref "U$1") (pin "P$15") (pinfunction "P$15_P$15") (pintype "bidirectional"))
    )
    (net (code "113") (name "unconnected-(U$1-PadP$16)") (class "Default")
      (node (ref "U$1") (pin "P$16") (pinfunction "P$16_P$16") (pintype "bidirectional"))
    )
    (net (code "114") (name "unconnected-(U$1-PadP$17)") (class "Default")
      (node (ref "U$1") (pin "P$17") (pinfunction "P$17_P$17") (pintype "bidirectional"))
    )
    (net (code "115") (name "unconnected-(U$1-PadP$18)") (class "Default")
      (node (ref "U$1") (pin "P$18") (pinfunction "P$18_P$18") (pintype "bidirectional"))
    )
    (net (code "116") (name "unconnected-(U$1-PadP$19)") (class "Default")
      (node (ref "U$1") (pin "P$19") (pinfunction "P$19_P$19") (pintype "bidirectional"))
    )
    (net (code "117") (name "unconnected-(U$1-PadP$21)") (class "Default")
      (node (ref "U$1") (pin "P$21") (pinfunction "P$21_P$21") (pintype "bidirectional"))
    )
    (net (code "118") (name "unconnected-(U$1-PadP$29)") (class "Default")
      (node (ref "U$1") (pin "P$29") (pinfunction "P$29_P$29") (pintype "bidirectional"))
    )
    (net (code "119") (name "unconnected-(U1-PA12{slash}TIM1_ETR{slash}USART1_RTS{slash}SAI2_FS_B{slash}CAN1_TX{slash}OTG_FS_DP{slash}EVENTOUT-Pad45)") (class "Default")
      (node (ref "U1") (pin "45") (pinfunction "PA12/TIM1_ETR/USART1_RTS/SAI2_FS_B/CAN1_TX/OTG_FS_DP/EVENTOUT_45") (pintype "bidirectional"))
    )
    (net (code "120") (name "unconnected-(U1-PB2-BOOT1(PB2){slash}TIM2_CH4{slash}SAI1_SD_A{slash}SPI3_MOSI{slash}I2S3_SD{slash}QUADSPI_CLK{slash}OTG_HS_ULPI_D4{slash}SDIO_CK{slash}EVENTOUT-Pad28)") (class "Default")
      (node (ref "U1") (pin "28") (pinfunction "PB2-BOOT1(PB2)/TIM2_CH4/SAI1_SD_A/SPI3_MOSI/I2S3_SD/QUADSPI_CLK/OTG_HS_ULPI_D4/SDIO_CK/EVENTOUT_28") (pintype "bidirectional"))
    )
    (net (code "121") (name "unconnected-(U1-PB12{slash}TIM1_BKIN{slash}I2C2_SMBA{slash}SPI2_NSS{slash}I2S2_WS{slash}SAI1_SCK_B{slash}USART3_CK{slash}CAN2_RX{slash}OTG_HS_ULPI_D5{slash}OTG_HS_ID{slash}EVENTOUT-Pad33)") (class "Default")
      (node (ref "U1") (pin "33") (pinfunction "PB12/TIM1_BKIN/I2C2_SMBA/SPI2_NSS/I2S2_WS/SAI1_SCK_B/USART3_CK/CAN2_RX/OTG_HS_ULPI_D5/OTG_HS_ID/EVENTOUT_33") (pintype "bidirectional"))
    )
    (net (code "122") (name "unconnected-(U1-PC14-OSC32_IN(PC14){slash}EVENTOUT-Pad3)") (class "Default")
      (node (ref "U1") (pin "3") (pinfunction "PC14-OSC32_IN(PC14)/EVENTOUT_3") (pintype "bidirectional"))
    )
    (net (code "123") (name "unconnected-(U1-PC15-OSC32_OUT(PC15){slash}EVENTOUT-Pad4)") (class "Default")
      (node (ref "U1") (pin "4") (pinfunction "PC15-OSC32_OUT(PC15)/EVENTOUT_4") (pintype "bidirectional"))
    )
    (net (code "124") (name "unconnected-(U1-PH0-OSC_IN{slash}EVENTOUT-Pad5)") (class "Default")
      (node (ref "U1") (pin "5") (pinfunction "PH0-OSC_IN/EVENTOUT_5") (pintype "bidirectional"))
    )
    (net (code "125") (name "unconnected-(U1-PH1-OSC_OUT{slash}EVENTOUT-Pad6)") (class "Default")
      (node (ref "U1") (pin "6") (pinfunction "PH1-OSC_OUT/EVENTOUT_6") (pintype "bidirectional"))
    )
    (net (code "126") (name "unconnected-(U2-PA0-CK_IN-Pad6)") (class "Default")
      (node (ref "U2") (pin "6") (pinfunction "PA0-CK_IN_6") (pintype "bidirectional"))
    )
    (net (code "127") (name "unconnected-(U2-PA2-Pad8)") (class "Default")
      (node (ref "U2") (pin "8") (pinfunction "PA2_8") (pintype "bidirectional"))
    )
    (net (code "128") (name "unconnected-(U2-PA3-Pad9)") (class "Default")
      (node (ref "U2") (pin "9") (pinfunction "PA3_9") (pintype "bidirectional"))
    )
    (net (code "129") (name "unconnected-(U2-PB1-Pad14)") (class "Default")
      (node (ref "U2") (pin "14") (pinfunction "PB1_14") (pintype "bidirectional"))
    )
    (net (code "130") (name "unconnected-(U2-PC14-OSC32_IN-Pad2)") (class "Default")
      (node (ref "U2") (pin "2") (pinfunction "PC14-OSC32_IN_2") (pintype "bidirectional"))
    )
    (net (code "131") (name "unconnected-(U2-PC15-OSC32_OUT-Pad3)") (class "Default")
      (node (ref "U2") (pin "3") (pinfunction "PC15-OSC32_OUT_3") (pintype "bidirectional"))
    )
    (net (code "132") (name "unconnected-(U3-PA0-CK_IN-Pad6)") (class "Default")
      (node (ref "U3") (pin "6") (pinfunction "PA0-CK_IN_6") (pintype "bidirectional"))
    )
    (net (code "133") (name "unconnected-(U3-PA2-Pad8)") (class "Default")
      (node (ref "U3") (pin "8") (pinfunction "PA2_8") (pintype "bidirectional"))
    )
    (net (code "134") (name "unconnected-(U3-PA3-Pad9)") (class "Default")
      (node (ref "U3") (pin "9") (pinfunction "PA3_9") (pintype "bidirectional"))
    )
    (net (code "135") (name "unconnected-(U3-PB1-Pad14)") (class "Default")
      (node (ref "U3") (pin "14") (pinfunction "PB1_14") (pintype "bidirectional"))
    )
    (net (code "136") (name "unconnected-(U3-PC14-OSC32_IN-Pad2)") (class "Default")
      (node (ref "U3") (pin "2") (pinfunction "PC14-OSC32_IN_2") (pintype "bidirectional"))
    )
    (net (code "137") (name "unconnected-(U3-PC15-OSC32_OUT-Pad3)") (class "Default")
      (node (ref "U3") (pin "3") (pinfunction "PC15-OSC32_OUT_3") (pintype "bidirectional"))
    )
    (net (code "138") (name "unconnected-(U4-PA0-CK_IN-Pad6)") (class "Default")
      (node (ref "U4") (pin "6") (pinfunction "PA0-CK_IN_6") (pintype "bidirectional"))
    )
    (net (code "139") (name "unconnected-(U4-PA2-Pad8)") (class "Default")
      (node (ref "U4") (pin "8") (pinfunction "PA2_8") (pintype "bidirectional"))
    )
    (net (code "140") (name "unconnected-(U4-PA3-Pad9)") (class "Default")
      (node (ref "U4") (pin "9") (pinfunction "PA3_9") (pintype "bidirectional"))
    )
    (net (code "141") (name "unconnected-(U4-PB1-Pad14)") (class "Default")
      (node (ref "U4") (pin "14") (pinfunction "PB1_14") (pintype "bidirectional"))
    )
    (net (code "142") (name "unconnected-(U4-PC14-OSC32_IN-Pad2)") (class "Default")
      (node (ref "U4") (pin "2") (pinfunction "PC14-OSC32_IN_2") (pintype "bidirectional"))
    )
    (net (code "143") (name "unconnected-(U4-PC15-OSC32_OUT-Pad3)") (class "Default")
      (node (ref "U4") (pin "3") (pinfunction "PC15-OSC32_OUT_3") (pintype "bidirectional"))
    )
    (net (code "144") (name "unconnected-(U5-PA0-CK_IN-Pad6)") (class "Default")
      (node (ref "U5") (pin "6") (pinfunction "PA0-CK_IN_6") (pintype "bidirectional"))
    )
    (net (code "145") (name "unconnected-(U5-PA2-Pad8)") (class "Default")
      (node (ref "U5") (pin "8") (pinfunction "PA2_8") (pintype "bidirectional"))
    )
    (net (code "146") (name "unconnected-(U5-PA3-Pad9)") (class "Default")
      (node (ref "U5") (pin "9") (pinfunction "PA3_9") (pintype "bidirectional"))
    )
    (net (code "147") (name "unconnected-(U5-PB1-Pad14)") (class "Default")
      (node (ref "U5") (pin "14") (pinfunction "PB1_14") (pintype "bidirectional"))
    )
    (net (code "148") (name "unconnected-(U5-PC14-OSC32_IN-Pad2)") (class "Default")
      (node (ref "U5") (pin "2") (pinfunction "PC14-OSC32_IN_2") (pintype "bidirectional"))
    )
    (net (code "149") (name "unconnected-(U5-PC15-OSC32_OUT-Pad3)") (class "Default")
      (node (ref "U5") (pin "3") (pinfunction "PC15-OSC32_OUT_3") (pintype "bidirectional"))
    )
    (net (code "150") (name "~{RESET-BALL}") (class "Default")
      (node (ref "SV1") (pin "15") (pinfunction "15_15") (pintype "passive"))
      (node (ref "U1") (pin "29") (pinfunction "PB10/TIM2_CH3/I2C2_SCL/SPI2_SCK/I2S2_CK/SAI1_SCK_A/USART3_TX/OTG_HS_ULPI_D3/EVENTOUT_29") (pintype "bidirectional"))
    )
  )
)
